# pcb.net
KiCad netlist of a schematic drawn in EasyEDA Pro
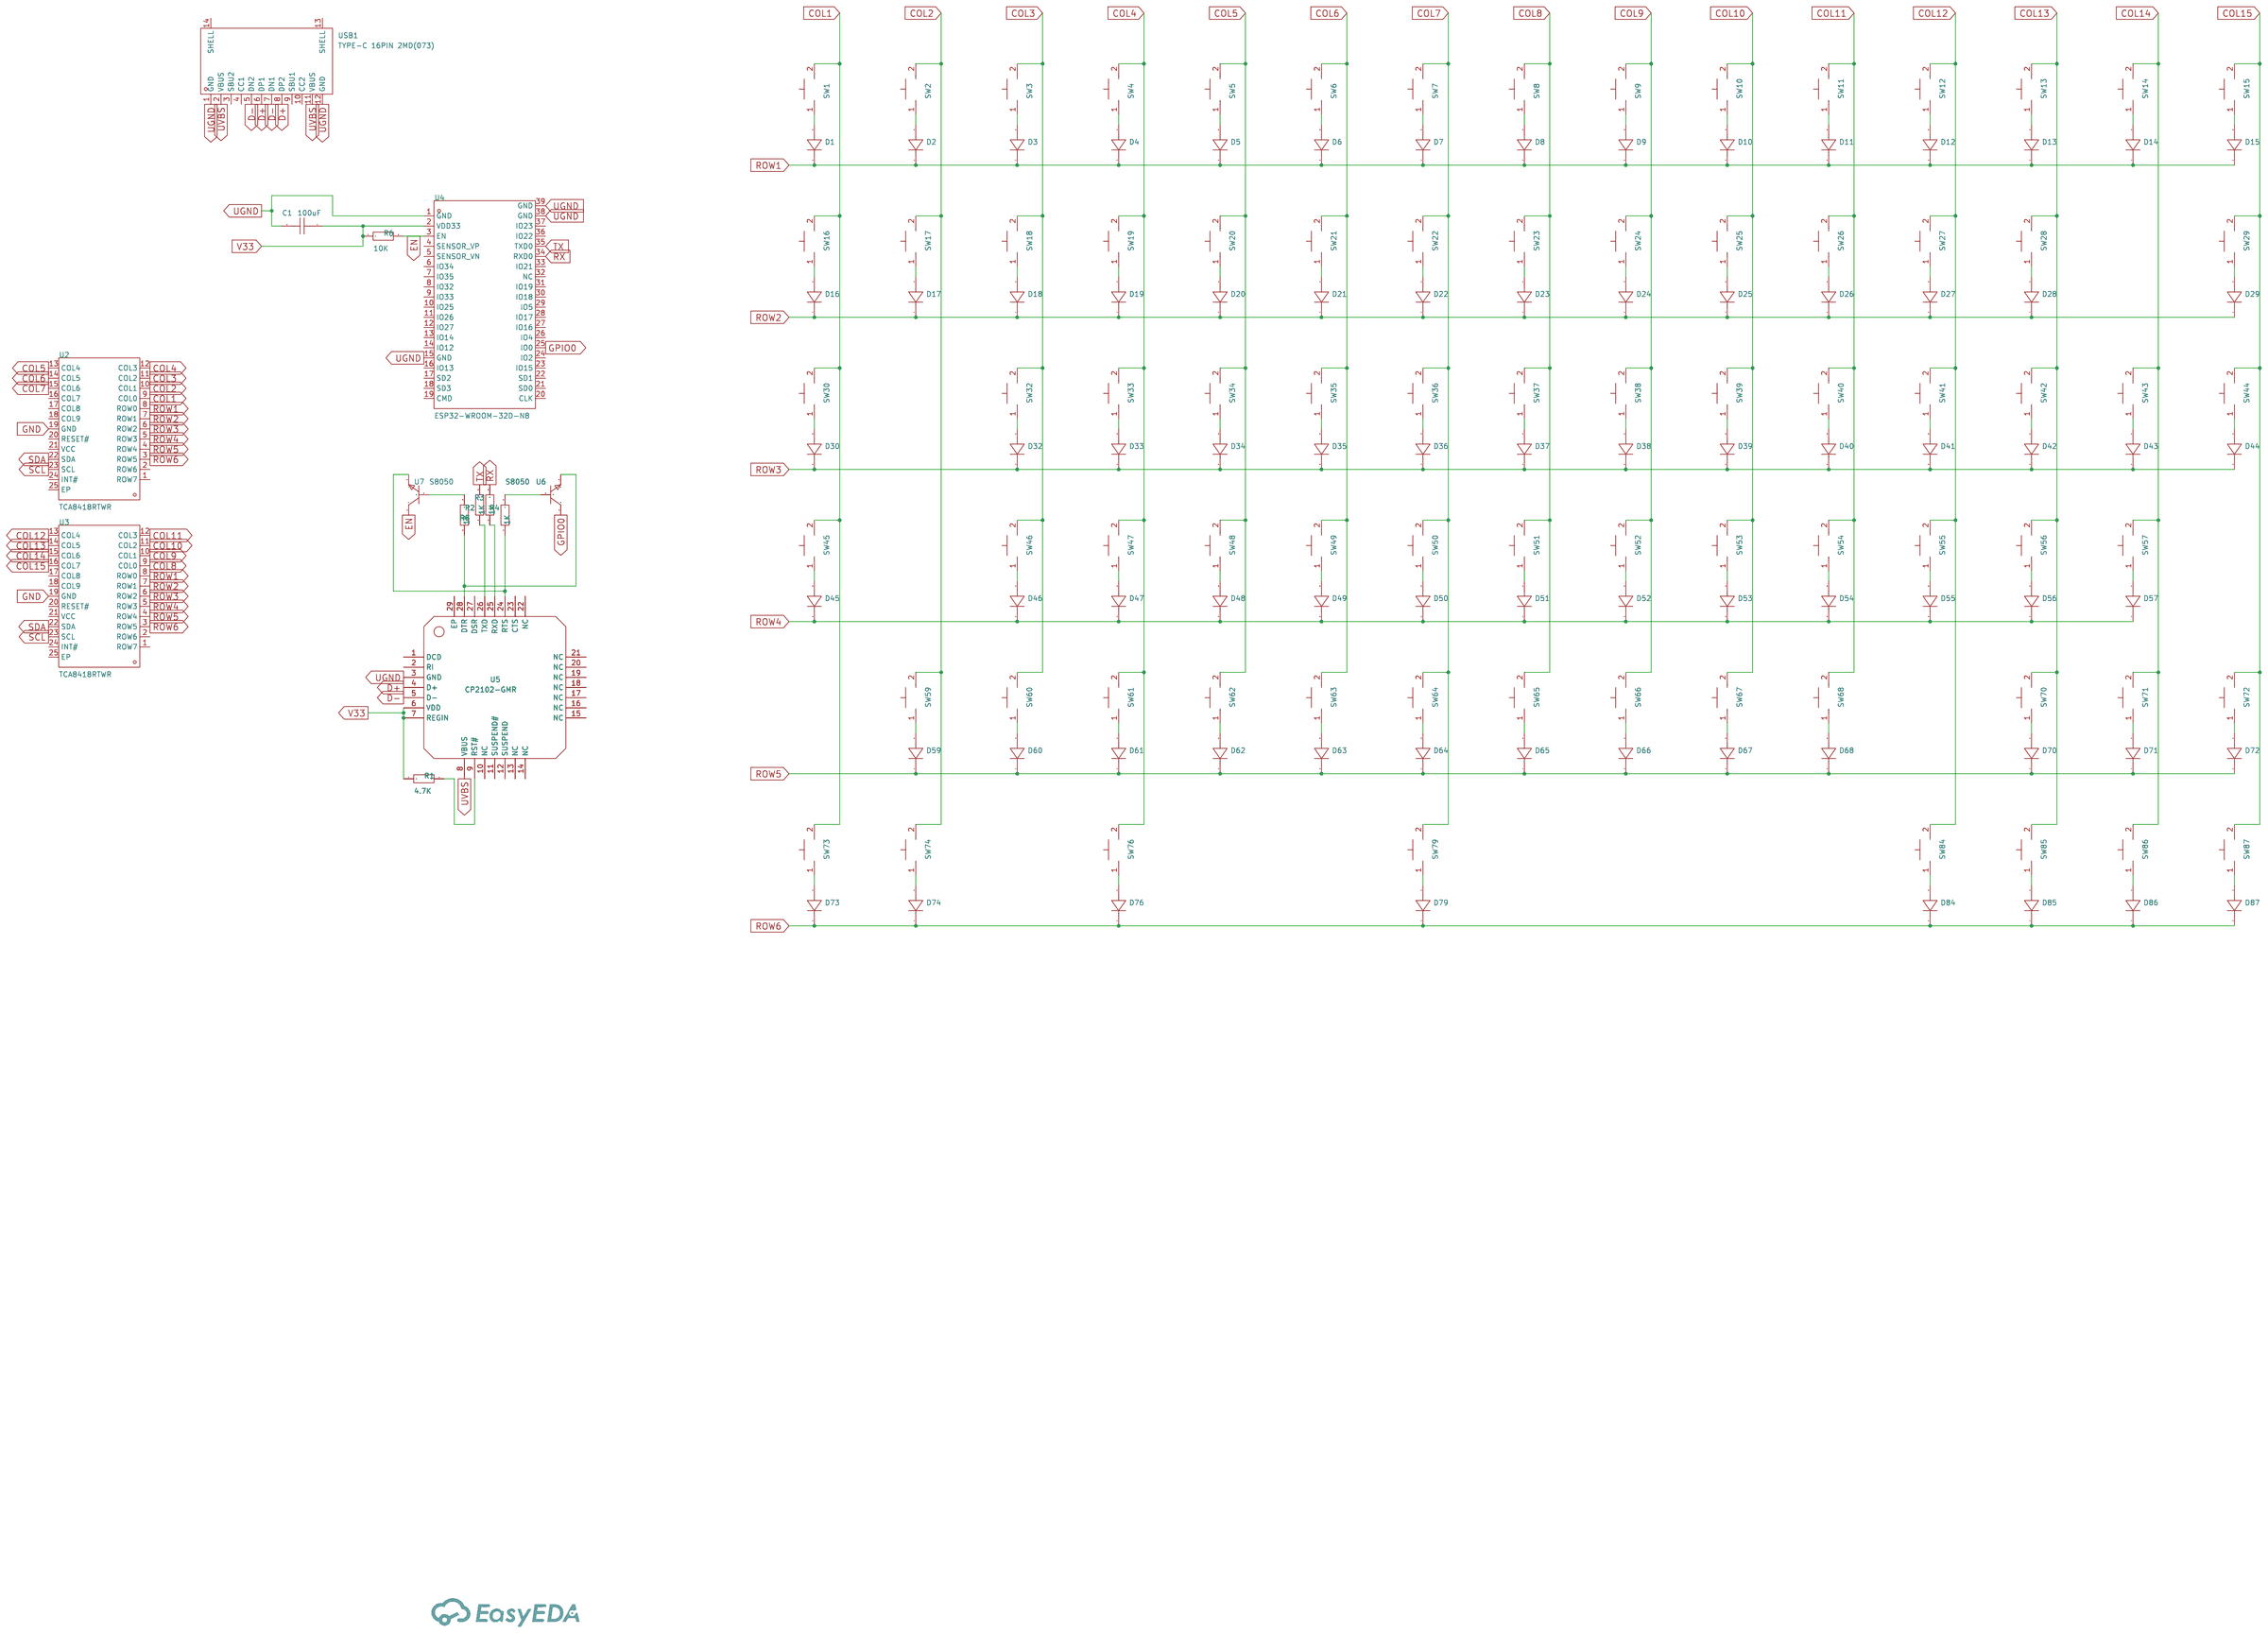
[diagram p0: schematic sheet]

(export (version "E")
  (design (tool "Eeschema 10.0.6"))
  (components
    (comp (ref "C1")
      (value "100uF")
      (footprint "easyedapro:C0603")
      (libsource (lib "easyedapro") (part "CAP"))
    )
    (comp (ref "D1")
      (value "~")
      (footprint "easyedapro:DO-41_BD2.4-L4.7-P8.70-D0.9-RD")
      (libsource (lib "easyedapro") (part "D_1N4007"))
    )
    (comp (ref "D2")
      (value "~")
      (footprint "easyedapro:DO-41_BD2.4-L4.7-P8.70-D0.9-RD")
      (libsource (lib "easyedapro") (part "D_1N4007"))
    )
    (comp (ref "D3")
      (value "~")
      (footprint "easyedapro:DO-41_BD2.4-L4.7-P8.70-D0.9-RD")
      (libsource (lib "easyedapro") (part "D_1N4007"))
    )
    (comp (ref "D4")
      (value "~")
      (footprint "easyedapro:DO-41_BD2.4-L4.7-P8.70-D0.9-RD")
      (libsource (lib "easyedapro") (part "D_1N4007"))
    )
    (comp (ref "D5")
      (value "~")
      (footprint "easyedapro:DO-41_BD2.4-L4.7-P8.70-D0.9-RD")
      (libsource (lib "easyedapro") (part "D_1N4007"))
    )
    (comp (ref "D6")
      (value "~")
      (footprint "easyedapro:DO-41_BD2.4-L4.7-P8.70-D0.9-RD")
      (libsource (lib "easyedapro") (part "D_1N4007"))
    )
    (comp (ref "D7")
      (value "~")
      (footprint "easyedapro:DO-41_BD2.4-L4.7-P8.70-D0.9-RD")
      (libsource (lib "easyedapro") (part "D_1N4007"))
    )
    (comp (ref "D8")
      (value "~")
      (footprint "easyedapro:DO-41_BD2.4-L4.7-P8.70-D0.9-RD")
      (libsource (lib "easyedapro") (part "D_1N4007"))
    )
    (comp (ref "D9")
      (value "~")
      (footprint "easyedapro:DO-41_BD2.4-L4.7-P8.70-D0.9-RD")
      (libsource (lib "easyedapro") (part "D_1N4007"))
    )
    (comp (ref "D10")
      (value "~")
      (footprint "easyedapro:DO-41_BD2.4-L4.7-P8.70-D0.9-RD")
      (libsource (lib "easyedapro") (part "D_1N4007"))
    )
    (comp (ref "D11")
      (value "~")
      (footprint "easyedapro:DO-41_BD2.4-L4.7-P8.70-D0.9-RD")
      (libsource (lib "easyedapro") (part "D_1N4007"))
    )
    (comp (ref "D12")
      (value "~")
      (footprint "easyedapro:DO-41_BD2.4-L4.7-P8.70-D0.9-RD")
      (libsource (lib "easyedapro") (part "D_1N4007"))
    )
    (comp (ref "D13")
      (value "~")
      (footprint "easyedapro:DO-41_BD2.4-L4.7-P8.70-D0.9-RD")
      (libsource (lib "easyedapro") (part "D_1N4007"))
    )
    (comp (ref "D14")
      (value "~")
      (footprint "easyedapro:DO-41_BD2.4-L4.7-P8.70-D0.9-RD")
      (libsource (lib "easyedapro") (part "D_1N4007"))
    )
    (comp (ref "D15")
      (value "~")
      (footprint "easyedapro:DO-41_BD2.4-L4.7-P8.70-D0.9-RD")
      (libsource (lib "easyedapro") (part "D_1N4007"))
    )
    (comp (ref "D16")
      (value "~")
      (footprint "easyedapro:DO-41_BD2.4-L4.7-P8.70-D0.9-RD")
      (libsource (lib "easyedapro") (part "D_1N4007"))
    )
    (comp (ref "D17")
      (value "~")
      (footprint "easyedapro:DO-41_BD2.4-L4.7-P8.70-D0.9-RD")
      (libsource (lib "easyedapro") (part "D_1N4007"))
    )
    (comp (ref "D18")
      (value "~")
      (footprint "easyedapro:DO-41_BD2.4-L4.7-P8.70-D0.9-RD")
      (libsource (lib "easyedapro") (part "D_1N4007"))
    )
    (comp (ref "D19")
      (value "~")
      (footprint "easyedapro:DO-41_BD2.4-L4.7-P8.70-D0.9-RD")
      (libsource (lib "easyedapro") (part "D_1N4007"))
    )
    (comp (ref "D20")
      (value "~")
      (footprint "easyedapro:DO-41_BD2.4-L4.7-P8.70-D0.9-RD")
      (libsource (lib "easyedapro") (part "D_1N4007"))
    )
    (comp (ref "D21")
      (value "~")
      (footprint "easyedapro:DO-41_BD2.4-L4.7-P8.70-D0.9-RD")
      (libsource (lib "easyedapro") (part "D_1N4007"))
    )
    (comp (ref "D22")
      (value "~")
      (footprint "easyedapro:DO-41_BD2.4-L4.7-P8.70-D0.9-RD")
      (libsource (lib "easyedapro") (part "D_1N4007"))
    )
    (comp (ref "D23")
      (value "~")
      (footprint "easyedapro:DO-41_BD2.4-L4.7-P8.70-D0.9-RD")
      (libsource (lib "easyedapro") (part "D_1N4007"))
    )
    (comp (ref "D24")
      (value "~")
      (footprint "easyedapro:DO-41_BD2.4-L4.7-P8.70-D0.9-RD")
      (libsource (lib "easyedapro") (part "D_1N4007"))
    )
    (comp (ref "D25")
      (value "~")
      (footprint "easyedapro:DO-41_BD2.4-L4.7-P8.70-D0.9-RD")
      (libsource (lib "easyedapro") (part "D_1N4007"))
    )
    (comp (ref "D26")
      (value "~")
      (footprint "easyedapro:DO-41_BD2.4-L4.7-P8.70-D0.9-RD")
      (libsource (lib "easyedapro") (part "D_1N4007"))
    )
    (comp (ref "D27")
      (value "~")
      (footprint "easyedapro:DO-41_BD2.4-L4.7-P8.70-D0.9-RD")
      (libsource (lib "easyedapro") (part "D_1N4007"))
    )
    (comp (ref "D28")
      (value "~")
      (footprint "easyedapro:DO-41_BD2.4-L4.7-P8.70-D0.9-RD")
      (libsource (lib "easyedapro") (part "D_1N4007"))
    )
    (comp (ref "D29")
      (value "~")
      (footprint "easyedapro:DO-41_BD2.4-L4.7-P8.70-D0.9-RD")
      (libsource (lib "easyedapro") (part "D_1N4007"))
    )
    (comp (ref "D30")
      (value "~")
      (footprint "easyedapro:DO-41_BD2.4-L4.7-P8.70-D0.9-RD")
      (libsource (lib "easyedapro") (part "D_1N4007"))
    )
    (comp (ref "D32")
      (value "~")
      (footprint "easyedapro:DO-41_BD2.4-L4.7-P8.70-D0.9-RD")
      (libsource (lib "easyedapro") (part "D_1N4007"))
    )
    (comp (ref "D33")
      (value "~")
      (footprint "easyedapro:DO-41_BD2.4-L4.7-P8.70-D0.9-RD")
      (libsource (lib "easyedapro") (part "D_1N4007"))
    )
    (comp (ref "D34")
      (value "~")
      (footprint "easyedapro:DO-41_BD2.4-L4.7-P8.70-D0.9-RD")
      (libsource (lib "easyedapro") (part "D_1N4007"))
    )
    (comp (ref "D35")
      (value "~")
      (footprint "easyedapro:DO-41_BD2.4-L4.7-P8.70-D0.9-RD")
      (libsource (lib "easyedapro") (part "D_1N4007"))
    )
    (comp (ref "D36")
      (value "~")
      (footprint "easyedapro:DO-41_BD2.4-L4.7-P8.70-D0.9-RD")
      (libsource (lib "easyedapro") (part "D_1N4007"))
    )
    (comp (ref "D37")
      (value "~")
      (footprint "easyedapro:DO-41_BD2.4-L4.7-P8.70-D0.9-RD")
      (libsource (lib "easyedapro") (part "D_1N4007"))
    )
    (comp (ref "D38")
      (value "~")
      (footprint "easyedapro:DO-41_BD2.4-L4.7-P8.70-D0.9-RD")
      (libsource (lib "easyedapro") (part "D_1N4007"))
    )
    (comp (ref "D39")
      (value "~")
      (footprint "easyedapro:DO-41_BD2.4-L4.7-P8.70-D0.9-RD")
      (libsource (lib "easyedapro") (part "D_1N4007"))
    )
    (comp (ref "D40")
      (value "~")
      (footprint "easyedapro:DO-41_BD2.4-L4.7-P8.70-D0.9-RD")
      (libsource (lib "easyedapro") (part "D_1N4007"))
    )
    (comp (ref "D41")
      (value "~")
      (footprint "easyedapro:DO-41_BD2.4-L4.7-P8.70-D0.9-RD")
      (libsource (lib "easyedapro") (part "D_1N4007"))
    )
    (comp (ref "D42")
      (value "~")
      (footprint "easyedapro:DO-41_BD2.4-L4.7-P8.70-D0.9-RD")
      (libsource (lib "easyedapro") (part "D_1N4007"))
    )
    (comp (ref "D43")
      (value "~")
      (footprint "easyedapro:DO-41_BD2.4-L4.7-P8.70-D0.9-RD")
      (libsource (lib "easyedapro") (part "D_1N4007"))
    )
    (comp (ref "D44")
      (value "~")
      (footprint "easyedapro:DO-41_BD2.4-L4.7-P8.70-D0.9-RD")
      (libsource (lib "easyedapro") (part "D_1N4007"))
    )
    (comp (ref "D45")
      (value "~")
      (footprint "easyedapro:DO-41_BD2.4-L4.7-P8.70-D0.9-RD")
      (libsource (lib "easyedapro") (part "D_1N4007"))
    )
    (comp (ref "D46")
      (value "~")
      (footprint "easyedapro:DO-41_BD2.4-L4.7-P8.70-D0.9-RD")
      (libsource (lib "easyedapro") (part "D_1N4007"))
    )
    (comp (ref "D47")
      (value "~")
      (footprint "easyedapro:DO-41_BD2.4-L4.7-P8.70-D0.9-RD")
      (libsource (lib "easyedapro") (part "D_1N4007"))
    )
    (comp (ref "D48")
      (value "~")
      (footprint "easyedapro:DO-41_BD2.4-L4.7-P8.70-D0.9-RD")
      (libsource (lib "easyedapro") (part "D_1N4007"))
    )
    (comp (ref "D49")
      (value "~")
      (footprint "easyedapro:DO-41_BD2.4-L4.7-P8.70-D0.9-RD")
      (libsource (lib "easyedapro") (part "D_1N4007"))
    )
    (comp (ref "D50")
      (value "~")
      (footprint "easyedapro:DO-41_BD2.4-L4.7-P8.70-D0.9-RD")
      (libsource (lib "easyedapro") (part "D_1N4007"))
    )
    (comp (ref "D51")
      (value "~")
      (footprint "easyedapro:DO-41_BD2.4-L4.7-P8.70-D0.9-RD")
      (libsource (lib "easyedapro") (part "D_1N4007"))
    )
    (comp (ref "D52")
      (value "~")
      (footprint "easyedapro:DO-41_BD2.4-L4.7-P8.70-D0.9-RD")
      (libsource (lib "easyedapro") (part "D_1N4007"))
    )
    (comp (ref "D53")
      (value "~")
      (footprint "easyedapro:DO-41_BD2.4-L4.7-P8.70-D0.9-RD")
      (libsource (lib "easyedapro") (part "D_1N4007"))
    )
    (comp (ref "D54")
      (value "~")
      (footprint "easyedapro:DO-41_BD2.4-L4.7-P8.70-D0.9-RD")
      (libsource (lib "easyedapro") (part "D_1N4007"))
    )
    (comp (ref "D55")
      (value "~")
      (footprint "easyedapro:DO-41_BD2.4-L4.7-P8.70-D0.9-RD")
      (libsource (lib "easyedapro") (part "D_1N4007"))
    )
    (comp (ref "D56")
      (value "~")
      (footprint "easyedapro:DO-41_BD2.4-L4.7-P8.70-D0.9-RD")
      (libsource (lib "easyedapro") (part "D_1N4007"))
    )
    (comp (ref "D57")
      (value "~")
      (footprint "easyedapro:DO-41_BD2.4-L4.7-P8.70-D0.9-RD")
      (libsource (lib "easyedapro") (part "D_1N4007"))
    )
    (comp (ref "D59")
      (value "~")
      (footprint "easyedapro:DO-41_BD2.4-L4.7-P8.70-D0.9-RD")
      (libsource (lib "easyedapro") (part "D_1N4007"))
    )
    (comp (ref "D60")
      (value "~")
      (footprint "easyedapro:DO-41_BD2.4-L4.7-P8.70-D0.9-RD")
      (libsource (lib "easyedapro") (part "D_1N4007"))
    )
    (comp (ref "D61")
      (value "~")
      (footprint "easyedapro:DO-41_BD2.4-L4.7-P8.70-D0.9-RD")
      (libsource (lib "easyedapro") (part "D_1N4007"))
    )
    (comp (ref "D62")
      (value "~")
      (footprint "easyedapro:DO-41_BD2.4-L4.7-P8.70-D0.9-RD")
      (libsource (lib "easyedapro") (part "D_1N4007"))
    )
    (comp (ref "D63")
      (value "~")
      (footprint "easyedapro:DO-41_BD2.4-L4.7-P8.70-D0.9-RD")
      (libsource (lib "easyedapro") (part "D_1N4007"))
    )
    (comp (ref "D64")
      (value "~")
      (footprint "easyedapro:DO-41_BD2.4-L4.7-P8.70-D0.9-RD")
      (libsource (lib "easyedapro") (part "D_1N4007"))
    )
    (comp (ref "D65")
      (value "~")
      (footprint "easyedapro:DO-41_BD2.4-L4.7-P8.70-D0.9-RD")
      (libsource (lib "easyedapro") (part "D_1N4007"))
    )
    (comp (ref "D66")
      (value "~")
      (footprint "easyedapro:DO-41_BD2.4-L4.7-P8.70-D0.9-RD")
      (libsource (lib "easyedapro") (part "D_1N4007"))
    )
    (comp (ref "D67")
      (value "~")
      (footprint "easyedapro:DO-41_BD2.4-L4.7-P8.70-D0.9-RD")
      (libsource (lib "easyedapro") (part "D_1N4007"))
    )
    (comp (ref "D68")
      (value "~")
      (footprint "easyedapro:DO-41_BD2.4-L4.7-P8.70-D0.9-RD")
      (libsource (lib "easyedapro") (part "D_1N4007"))
    )
    (comp (ref "D70")
      (value "~")
      (footprint "easyedapro:DO-41_BD2.4-L4.7-P8.70-D0.9-RD")
      (libsource (lib "easyedapro") (part "D_1N4007"))
    )
    (comp (ref "D71")
      (value "~")
      (footprint "easyedapro:DO-41_BD2.4-L4.7-P8.70-D0.9-RD")
      (libsource (lib "easyedapro") (part "D_1N4007"))
    )
    (comp (ref "D72")
      (value "~")
      (footprint "easyedapro:DO-41_BD2.4-L4.7-P8.70-D0.9-RD")
      (libsource (lib "easyedapro") (part "D_1N4007"))
    )
    (comp (ref "D73")
      (value "~")
      (footprint "easyedapro:DO-41_BD2.4-L4.7-P8.70-D0.9-RD")
      (libsource (lib "easyedapro") (part "D_1N4007"))
    )
    (comp (ref "D74")
      (value "~")
      (footprint "easyedapro:DO-41_BD2.4-L4.7-P8.70-D0.9-RD")
      (libsource (lib "easyedapro") (part "D_1N4007"))
    )
    (comp (ref "D76")
      (value "~")
      (footprint "easyedapro:DO-41_BD2.4-L4.7-P8.70-D0.9-RD")
      (libsource (lib "easyedapro") (part "D_1N4007"))
    )
    (comp (ref "D79")
      (value "~")
      (footprint "easyedapro:DO-41_BD2.4-L4.7-P8.70-D0.9-RD")
      (libsource (lib "easyedapro") (part "D_1N4007"))
    )
    (comp (ref "D84")
      (value "~")
      (footprint "easyedapro:DO-41_BD2.4-L4.7-P8.70-D0.9-RD")
      (libsource (lib "easyedapro") (part "D_1N4007"))
    )
    (comp (ref "D85")
      (value "~")
      (footprint "easyedapro:DO-41_BD2.4-L4.7-P8.70-D0.9-RD")
      (libsource (lib "easyedapro") (part "D_1N4007"))
    )
    (comp (ref "D86")
      (value "~")
      (footprint "easyedapro:DO-41_BD2.4-L4.7-P8.70-D0.9-RD")
      (libsource (lib "easyedapro") (part "D_1N4007"))
    )
    (comp (ref "D87")
      (value "~")
      (footprint "easyedapro:DO-41_BD2.4-L4.7-P8.70-D0.9-RD")
      (libsource (lib "easyedapro") (part "D_1N4007"))
    )
    (comp (ref "R1")
      (value "4.7K")
      (footprint "easyedapro:R0603")
      (libsource (lib "easyedapro") (part "Res"))
    )
    (comp (ref "R2") (value "1K") (footprint "easyedapro:R0603") (libsource (lib "easyedapro") (part "Res")))
    (comp (ref "R3") (value "1K") (footprint "easyedapro:R0603") (libsource (lib "easyedapro") (part "Res")))
    (comp (ref "R4") (value "1K") (footprint "easyedapro:R0603") (libsource (lib "easyedapro") (part "Res")))
    (comp (ref "R5") (value "1K") (footprint "easyedapro:R0603") (libsource (lib "easyedapro") (part "Res")))
    (comp (ref "R6") (value "10K") (footprint "easyedapro:R0603") (libsource (lib "easyedapro") (part "Res")))
    (comp (ref "SW1")
      (value "CPG151101S11-16")
      (footprint "easyedapro:SMD_KEYBOARD-SW")
      (fields (field (name "Manufacturer") "HanElectricity(瀚源)"))
      (libsource (lib "easyedapro") (part "CPG151101S11-16_C41430893"))
    )
    (comp (ref "SW2")
      (value "CPG151101S11-16")
      (footprint "easyedapro:SMD_KEYBOARD-SW")
      (fields (field (name "Manufacturer") "HanElectricity(瀚源)"))
      (libsource (lib "easyedapro") (part "CPG151101S11-16_C41430893"))
    )
    (comp (ref "SW3")
      (value "CPG151101S11-16")
      (footprint "easyedapro:SMD_KEYBOARD-SW")
      (fields (field (name "Manufacturer") "HanElectricity(瀚源)"))
      (libsource (lib "easyedapro") (part "CPG151101S11-16_C41430893"))
    )
    (comp (ref "SW4")
      (value "CPG151101S11-16")
      (footprint "easyedapro:SMD_KEYBOARD-SW")
      (fields (field (name "Manufacturer") "HanElectricity(瀚源)"))
      (libsource (lib "easyedapro") (part "CPG151101S11-16_C41430893"))
    )
    (comp (ref "SW5")
      (value "CPG151101S11-16")
      (footprint "easyedapro:SMD_KEYBOARD-SW")
      (fields (field (name "Manufacturer") "HanElectricity(瀚源)"))
      (libsource (lib "easyedapro") (part "CPG151101S11-16_C41430893"))
    )
    (comp (ref "SW6")
      (value "CPG151101S11-16")
      (footprint "easyedapro:SMD_KEYBOARD-SW")
      (fields (field (name "Manufacturer") "HanElectricity(瀚源)"))
      (libsource (lib "easyedapro") (part "CPG151101S11-16_C41430893"))
    )
    (comp (ref "SW7")
      (value "CPG151101S11-16")
      (footprint "easyedapro:SMD_KEYBOARD-SW")
      (fields (field (name "Manufacturer") "HanElectricity(瀚源)"))
      (libsource (lib "easyedapro") (part "CPG151101S11-16_C41430893"))
    )
    (comp (ref "SW8")
      (value "CPG151101S11-16")
      (footprint "easyedapro:SMD_KEYBOARD-SW")
      (fields (field (name "Manufacturer") "HanElectricity(瀚源)"))
      (libsource (lib "easyedapro") (part "CPG151101S11-16_C41430893"))
    )
    (comp (ref "SW9")
      (value "CPG151101S11-16")
      (footprint "easyedapro:SMD_KEYBOARD-SW")
      (fields (field (name "Manufacturer") "HanElectricity(瀚源)"))
      (libsource (lib "easyedapro") (part "CPG151101S11-16_C41430893"))
    )
    (comp (ref "SW10")
      (value "CPG151101S11-16")
      (footprint "easyedapro:SMD_KEYBOARD-SW")
      (fields (field (name "Manufacturer") "HanElectricity(瀚源)"))
      (libsource (lib "easyedapro") (part "CPG151101S11-16_C41430893"))
    )
    (comp (ref "SW11")
      (value "CPG151101S11-16")
      (footprint "easyedapro:SMD_KEYBOARD-SW")
      (fields (field (name "Manufacturer") "HanElectricity(瀚源)"))
      (libsource (lib "easyedapro") (part "CPG151101S11-16_C41430893"))
    )
    (comp (ref "SW12")
      (value "CPG151101S11-16")
      (footprint "easyedapro:SMD_KEYBOARD-SW")
      (fields (field (name "Manufacturer") "HanElectricity(瀚源)"))
      (libsource (lib "easyedapro") (part "CPG151101S11-16_C41430893"))
    )
    (comp (ref "SW13")
      (value "CPG151101S11-16")
      (footprint "easyedapro:SMD_KEYBOARD-SW")
      (fields (field (name "Manufacturer") "HanElectricity(瀚源)"))
      (libsource (lib "easyedapro") (part "CPG151101S11-16_C41430893"))
    )
    (comp (ref "SW14")
      (value "CPG151101S11-16")
      (footprint "easyedapro:SMD_KEYBOARD-SW")
      (fields (field (name "Manufacturer") "HanElectricity(瀚源)"))
      (libsource (lib "easyedapro") (part "CPG151101S11-16_C41430893"))
    )
    (comp (ref "SW15")
      (value "CPG151101S11-16")
      (footprint "easyedapro:SMD_KEYBOARD-SW")
      (fields (field (name "Manufacturer") "HanElectricity(瀚源)"))
      (libsource (lib "easyedapro") (part "CPG151101S11-16_C41430893"))
    )
    (comp (ref "SW16")
      (value "CPG151101S11-16")
      (footprint "easyedapro:SMD_KEYBOARD-SW")
      (fields (field (name "Manufacturer") "HanElectricity(瀚源)"))
      (libsource (lib "easyedapro") (part "CPG151101S11-16_C41430893"))
    )
    (comp (ref "SW17")
      (value "CPG151101S11-16")
      (footprint "easyedapro:SMD_KEYBOARD-SW")
      (fields (field (name "Manufacturer") "HanElectricity(瀚源)"))
      (libsource (lib "easyedapro") (part "CPG151101S11-16_C41430893"))
    )
    (comp (ref "SW18")
      (value "CPG151101S11-16")
      (footprint "easyedapro:SMD_KEYBOARD-SW")
      (fields (field (name "Manufacturer") "HanElectricity(瀚源)"))
      (libsource (lib "easyedapro") (part "CPG151101S11-16_C41430893"))
    )
    (comp (ref "SW19")
      (value "CPG151101S11-16")
      (footprint "easyedapro:SMD_KEYBOARD-SW")
      (fields (field (name "Manufacturer") "HanElectricity(瀚源)"))
      (libsource (lib "easyedapro") (part "CPG151101S11-16_C41430893"))
    )
    (comp (ref "SW20")
      (value "CPG151101S11-16")
      (footprint "easyedapro:SMD_KEYBOARD-SW")
      (fields (field (name "Manufacturer") "HanElectricity(瀚源)"))
      (libsource (lib "easyedapro") (part "CPG151101S11-16_C41430893"))
    )
    (comp (ref "SW21")
      (value "CPG151101S11-16")
      (footprint "easyedapro:SMD_KEYBOARD-SW")
      (fields (field (name "Manufacturer") "HanElectricity(瀚源)"))
      (libsource (lib "easyedapro") (part "CPG151101S11-16_C41430893"))
    )
    (comp (ref "SW22")
      (value "CPG151101S11-16")
      (footprint "easyedapro:SMD_KEYBOARD-SW")
      (fields (field (name "Manufacturer") "HanElectricity(瀚源)"))
      (libsource (lib "easyedapro") (part "CPG151101S11-16_C41430893"))
    )
    (comp (ref "SW23")
      (value "CPG151101S11-16")
      (footprint "easyedapro:SMD_KEYBOARD-SW")
      (fields (field (name "Manufacturer") "HanElectricity(瀚源)"))
      (libsource (lib "easyedapro") (part "CPG151101S11-16_C41430893"))
    )
    (comp (ref "SW24")
      (value "CPG151101S11-16")
      (footprint "easyedapro:SMD_KEYBOARD-SW")
      (fields (field (name "Manufacturer") "HanElectricity(瀚源)"))
      (libsource (lib "easyedapro") (part "CPG151101S11-16_C41430893"))
    )
    (comp (ref "SW25")
      (value "CPG151101S11-16")
      (footprint "easyedapro:SMD_KEYBOARD-SW")
      (fields (field (name "Manufacturer") "HanElectricity(瀚源)"))
      (libsource (lib "easyedapro") (part "CPG151101S11-16_C41430893"))
    )
    (comp (ref "SW26")
      (value "CPG151101S11-16")
      (footprint "easyedapro:SMD_KEYBOARD-SW")
      (fields (field (name "Manufacturer") "HanElectricity(瀚源)"))
      (libsource (lib "easyedapro") (part "CPG151101S11-16_C41430893"))
    )
    (comp (ref "SW27")
      (value "CPG151101S11-16")
      (footprint "easyedapro:SMD_KEYBOARD-SW")
      (fields (field (name "Manufacturer") "HanElectricity(瀚源)"))
      (libsource (lib "easyedapro") (part "CPG151101S11-16_C41430893"))
    )
    (comp (ref "SW28")
      (value "CPG151101S11-16")
      (footprint "easyedapro:SMD_KEYBOARD-SW")
      (fields (field (name "Manufacturer") "HanElectricity(瀚源)"))
      (libsource (lib "easyedapro") (part "CPG151101S11-16_C41430893"))
    )
    (comp (ref "SW29")
      (value "CPG151101S11-16")
      (footprint "easyedapro:SMD_KEYBOARD-SW")
      (fields (field (name "Manufacturer") "HanElectricity(瀚源)"))
      (libsource (lib "easyedapro") (part "CPG151101S11-16_C41430893"))
    )
    (comp (ref "SW30")
      (value "CPG151101S11-16")
      (footprint "easyedapro:SMD_KEYBOARD-SW")
      (fields (field (name "Manufacturer") "HanElectricity(瀚源)"))
      (libsource (lib "easyedapro") (part "CPG151101S11-16_C41430893"))
    )
    (comp (ref "SW32")
      (value "CPG151101S11-16")
      (footprint "easyedapro:SMD_KEYBOARD-SW")
      (fields (field (name "Manufacturer") "HanElectricity(瀚源)"))
      (libsource (lib "easyedapro") (part "CPG151101S11-16_C41430893"))
    )
    (comp (ref "SW33")
      (value "CPG151101S11-16")
      (footprint "easyedapro:SMD_KEYBOARD-SW")
      (fields (field (name "Manufacturer") "HanElectricity(瀚源)"))
      (libsource (lib "easyedapro") (part "CPG151101S11-16_C41430893"))
    )
    (comp (ref "SW34")
      (value "CPG151101S11-16")
      (footprint "easyedapro:SMD_KEYBOARD-SW")
      (fields (field (name "Manufacturer") "HanElectricity(瀚源)"))
      (libsource (lib "easyedapro") (part "CPG151101S11-16_C41430893"))
    )
    (comp (ref "SW35")
      (value "CPG151101S11-16")
      (footprint "easyedapro:SMD_KEYBOARD-SW")
      (fields (field (name "Manufacturer") "HanElectricity(瀚源)"))
      (libsource (lib "easyedapro") (part "CPG151101S11-16_C41430893"))
    )
    (comp (ref "SW36")
      (value "CPG151101S11-16")
      (footprint "easyedapro:SMD_KEYBOARD-SW")
      (fields (field (name "Manufacturer") "HanElectricity(瀚源)"))
      (libsource (lib "easyedapro") (part "CPG151101S11-16_C41430893"))
    )
    (comp (ref "SW37")
      (value "CPG151101S11-16")
      (footprint "easyedapro:SMD_KEYBOARD-SW")
      (fields (field (name "Manufacturer") "HanElectricity(瀚源)"))
      (libsource (lib "easyedapro") (part "CPG151101S11-16_C41430893"))
    )
    (comp (ref "SW38")
      (value "CPG151101S11-16")
      (footprint "easyedapro:SMD_KEYBOARD-SW")
      (fields (field (name "Manufacturer") "HanElectricity(瀚源)"))
      (libsource (lib "easyedapro") (part "CPG151101S11-16_C41430893"))
    )
    (comp (ref "SW39")
      (value "CPG151101S11-16")
      (footprint "easyedapro:SMD_KEYBOARD-SW")
      (fields (field (name "Manufacturer") "HanElectricity(瀚源)"))
      (libsource (lib "easyedapro") (part "CPG151101S11-16_C41430893"))
    )
    (comp (ref "SW40")
      (value "CPG151101S11-16")
      (footprint "easyedapro:SMD_KEYBOARD-SW")
      (fields (field (name "Manufacturer") "HanElectricity(瀚源)"))
      (libsource (lib "easyedapro") (part "CPG151101S11-16_C41430893"))
    )
    (comp (ref "SW41")
      (value "CPG151101S11-16")
      (footprint "easyedapro:SMD_KEYBOARD-SW")
      (fields (field (name "Manufacturer") "HanElectricity(瀚源)"))
      (libsource (lib "easyedapro") (part "CPG151101S11-16_C41430893"))
    )
    (comp (ref "SW42")
      (value "CPG151101S11-16")
      (footprint "easyedapro:SMD_KEYBOARD-SW")
      (fields (field (name "Manufacturer") "HanElectricity(瀚源)"))
      (libsource (lib "easyedapro") (part "CPG151101S11-16_C41430893"))
    )
    (comp (ref "SW43")
      (value "CPG151101S11-16")
      (footprint "easyedapro:SMD_KEYBOARD-SW")
      (fields (field (name "Manufacturer") "HanElectricity(瀚源)"))
      (libsource (lib "easyedapro") (part "CPG151101S11-16_C41430893"))
    )
    (comp (ref "SW44")
      (value "CPG151101S11-16")
      (footprint "easyedapro:SMD_KEYBOARD-SW")
      (fields (field (name "Manufacturer") "HanElectricity(瀚源)"))
      (libsource (lib "easyedapro") (part "CPG151101S11-16_C41430893"))
    )
    (comp (ref "SW45")
      (value "CPG151101S11-16")
      (footprint "easyedapro:SMD_KEYBOARD-SW")
      (fields (field (name "Manufacturer") "HanElectricity(瀚源)"))
      (libsource (lib "easyedapro") (part "CPG151101S11-16_C41430893"))
    )
    (comp (ref "SW46")
      (value "CPG151101S11-16")
      (footprint "easyedapro:SMD_KEYBOARD-SW")
      (fields (field (name "Manufacturer") "HanElectricity(瀚源)"))
      (libsource (lib "easyedapro") (part "CPG151101S11-16_C41430893"))
    )
    (comp (ref "SW47")
      (value "CPG151101S11-16")
      (footprint "easyedapro:SMD_KEYBOARD-SW")
      (fields (field (name "Manufacturer") "HanElectricity(瀚源)"))
      (libsource (lib "easyedapro") (part "CPG151101S11-16_C41430893"))
    )
    (comp (ref "SW48")
      (value "CPG151101S11-16")
      (footprint "easyedapro:SMD_KEYBOARD-SW")
      (fields (field (name "Manufacturer") "HanElectricity(瀚源)"))
      (libsource (lib "easyedapro") (part "CPG151101S11-16_C41430893"))
    )
    (comp (ref "SW49")
      (value "CPG151101S11-16")
      (footprint "easyedapro:SMD_KEYBOARD-SW")
      (fields (field (name "Manufacturer") "HanElectricity(瀚源)"))
      (libsource (lib "easyedapro") (part "CPG151101S11-16_C41430893"))
    )
    (comp (ref "SW50")
      (value "CPG151101S11-16")
      (footprint "easyedapro:SMD_KEYBOARD-SW")
      (fields (field (name "Manufacturer") "HanElectricity(瀚源)"))
      (libsource (lib "easyedapro") (part "CPG151101S11-16_C41430893"))
    )
    (comp (ref "SW51")
      (value "CPG151101S11-16")
      (footprint "easyedapro:SMD_KEYBOARD-SW")
      (fields (field (name "Manufacturer") "HanElectricity(瀚源)"))
      (libsource (lib "easyedapro") (part "CPG151101S11-16_C41430893"))
    )
    (comp (ref "SW52")
      (value "CPG151101S11-16")
      (footprint "easyedapro:SMD_KEYBOARD-SW")
      (fields (field (name "Manufacturer") "HanElectricity(瀚源)"))
      (libsource (lib "easyedapro") (part "CPG151101S11-16_C41430893"))
    )
    (comp (ref "SW53")
      (value "CPG151101S11-16")
      (footprint "easyedapro:SMD_KEYBOARD-SW")
      (fields (field (name "Manufacturer") "HanElectricity(瀚源)"))
      (libsource (lib "easyedapro") (part "CPG151101S11-16_C41430893"))
    )
    (comp (ref "SW54")
      (value "CPG151101S11-16")
      (footprint "easyedapro:SMD_KEYBOARD-SW")
      (fields (field (name "Manufacturer") "HanElectricity(瀚源)"))
      (libsource (lib "easyedapro") (part "CPG151101S11-16_C41430893"))
    )
    (comp (ref "SW55")
      (value "CPG151101S11-16")
      (footprint "easyedapro:SMD_KEYBOARD-SW")
      (fields (field (name "Manufacturer") "HanElectricity(瀚源)"))
      (libsource (lib "easyedapro") (part "CPG151101S11-16_C41430893"))
    )
    (comp (ref "SW56")
      (value "CPG151101S11-16")
      (footprint "easyedapro:SMD_KEYBOARD-SW")
      (fields (field (name "Manufacturer") "HanElectricity(瀚源)"))
      (libsource (lib "easyedapro") (part "CPG151101S11-16_C41430893"))
    )
    (comp (ref "SW57")
      (value "CPG151101S11-16")
      (footprint "easyedapro:SMD_KEYBOARD-SW")
      (fields (field (name "Manufacturer") "HanElectricity(瀚源)"))
      (libsource (lib "easyedapro") (part "CPG151101S11-16_C41430893"))
    )
    (comp (ref "SW59")
      (value "CPG151101S11-16")
      (footprint "easyedapro:SMD_KEYBOARD-SW")
      (fields (field (name "Manufacturer") "HanElectricity(瀚源)"))
      (libsource (lib "easyedapro") (part "CPG151101S11-16_C41430893"))
    )
    (comp (ref "SW60")
      (value "CPG151101S11-16")
      (footprint "easyedapro:SMD_KEYBOARD-SW")
      (fields (field (name "Manufacturer") "HanElectricity(瀚源)"))
      (libsource (lib "easyedapro") (part "CPG151101S11-16_C41430893"))
    )
    (comp (ref "SW61")
      (value "CPG151101S11-16")
      (footprint "easyedapro:SMD_KEYBOARD-SW")
      (fields (field (name "Manufacturer") "HanElectricity(瀚源)"))
      (libsource (lib "easyedapro") (part "CPG151101S11-16_C41430893"))
    )
    (comp (ref "SW62")
      (value "CPG151101S11-16")
      (footprint "easyedapro:SMD_KEYBOARD-SW")
      (fields (field (name "Manufacturer") "HanElectricity(瀚源)"))
      (libsource (lib "easyedapro") (part "CPG151101S11-16_C41430893"))
    )
    (comp (ref "SW63")
      (value "CPG151101S11-16")
      (footprint "easyedapro:SMD_KEYBOARD-SW")
      (fields (field (name "Manufacturer") "HanElectricity(瀚源)"))
      (libsource (lib "easyedapro") (part "CPG151101S11-16_C41430893"))
    )
    (comp (ref "SW64")
      (value "CPG151101S11-16")
      (footprint "easyedapro:SMD_KEYBOARD-SW")
      (fields (field (name "Manufacturer") "HanElectricity(瀚源)"))
      (libsource (lib "easyedapro") (part "CPG151101S11-16_C41430893"))
    )
    (comp (ref "SW65")
      (value "CPG151101S11-16")
      (footprint "easyedapro:SMD_KEYBOARD-SW")
      (fields (field (name "Manufacturer") "HanElectricity(瀚源)"))
      (libsource (lib "easyedapro") (part "CPG151101S11-16_C41430893"))
    )
    (comp (ref "SW66")
      (value "CPG151101S11-16")
      (footprint "easyedapro:SMD_KEYBOARD-SW")
      (fields (field (name "Manufacturer") "HanElectricity(瀚源)"))
      (libsource (lib "easyedapro") (part "CPG151101S11-16_C41430893"))
    )
    (comp (ref "SW67")
      (value "CPG151101S11-16")
      (footprint "easyedapro:SMD_KEYBOARD-SW")
      (fields (field (name "Manufacturer") "HanElectricity(瀚源)"))
      (libsource (lib "easyedapro") (part "CPG151101S11-16_C41430893"))
    )
    (comp (ref "SW68")
      (value "CPG151101S11-16")
      (footprint "easyedapro:SMD_KEYBOARD-SW")
      (fields (field (name "Manufacturer") "HanElectricity(瀚源)"))
      (libsource (lib "easyedapro") (part "CPG151101S11-16_C41430893"))
    )
    (comp (ref "SW70")
      (value "CPG151101S11-16")
      (footprint "easyedapro:SMD_KEYBOARD-SW")
      (fields (field (name "Manufacturer") "HanElectricity(瀚源)"))
      (libsource (lib "easyedapro") (part "CPG151101S11-16_C41430893"))
    )
    (comp (ref "SW71")
      (value "CPG151101S11-16")
      (footprint "easyedapro:SMD_KEYBOARD-SW")
      (fields (field (name "Manufacturer") "HanElectricity(瀚源)"))
      (libsource (lib "easyedapro") (part "CPG151101S11-16_C41430893"))
    )
    (comp (ref "SW72")
      (value "CPG151101S11-16")
      (footprint "easyedapro:SMD_KEYBOARD-SW")
      (fields (field (name "Manufacturer") "HanElectricity(瀚源)"))
      (libsource (lib "easyedapro") (part "CPG151101S11-16_C41430893"))
    )
    (comp (ref "SW73")
      (value "CPG151101S11-16")
      (footprint "easyedapro:SMD_KEYBOARD-SW")
      (fields (field (name "Manufacturer") "HanElectricity(瀚源)"))
      (libsource (lib "easyedapro") (part "CPG151101S11-16_C41430893"))
    )
    (comp (ref "SW74")
      (value "CPG151101S11-16")
      (footprint "easyedapro:SMD_KEYBOARD-SW")
      (fields (field (name "Manufacturer") "HanElectricity(瀚源)"))
      (libsource (lib "easyedapro") (part "CPG151101S11-16_C41430893"))
    )
    (comp (ref "SW76")
      (value "CPG151101S11-16")
      (footprint "easyedapro:SMD_KEYBOARD-SW")
      (fields (field (name "Manufacturer") "HanElectricity(瀚源)"))
      (libsource (lib "easyedapro") (part "CPG151101S11-16_C41430893"))
    )
    (comp (ref "SW79")
      (value "CPG151101S11-16")
      (footprint "easyedapro:SMD_KEYBOARD-SW")
      (fields (field (name "Manufacturer") "HanElectricity(瀚源)"))
      (libsource (lib "easyedapro") (part "CPG151101S11-16_C41430893"))
    )
    (comp (ref "SW84")
      (value "CPG151101S11-16")
      (footprint "easyedapro:SMD_KEYBOARD-SW")
      (fields (field (name "Manufacturer") "HanElectricity(瀚源)"))
      (libsource (lib "easyedapro") (part "CPG151101S11-16_C41430893"))
    )
    (comp (ref "SW85")
      (value "CPG151101S11-16")
      (footprint "easyedapro:SMD_KEYBOARD-SW")
      (fields (field (name "Manufacturer") "HanElectricity(瀚源)"))
      (libsource (lib "easyedapro") (part "CPG151101S11-16_C41430893"))
    )
    (comp (ref "SW86")
      (value "CPG151101S11-16")
      (footprint "easyedapro:SMD_KEYBOARD-SW")
      (fields (field (name "Manufacturer") "HanElectricity(瀚源)"))
      (libsource (lib "easyedapro") (part "CPG151101S11-16_C41430893"))
    )
    (comp (ref "SW87")
      (value "CPG151101S11-16")
      (footprint "easyedapro:SMD_KEYBOARD-SW")
      (fields (field (name "Manufacturer") "HanElectricity(瀚源)"))
      (libsource (lib "easyedapro") (part "CPG151101S11-16_C41430893"))
    )
    (comp (ref "U2")
      (value "TCA8418RTWR")
      (footprint "easyedapro:WQFN-24_L4.0-W4.0-P0.50-TL-EP2.5")
      (fields (field (name "Manufacturer") "TI(德州仪器)"))
      (libsource (lib "easyedapro") (part "TCA8418RTWR"))
    )
    (comp (ref "U3")
      (value "TCA8418RTWR")
      (footprint "easyedapro:WQFN-24_L4.0-W4.0-P0.50-TL-EP2.5")
      (fields (field (name "Manufacturer") "TI(德州仪器)"))
      (libsource (lib "easyedapro") (part "TCA8418RTWR"))
    )
    (comp (ref "U4")
      (value "ESP32-WROOM-32D-N8")
      (footprint "easyedapro:WIFIM-SMD_39P-L25.5-W18.0-P1.27")
      (fields (field (name "Manufacturer") "ESPRESSIF(乐鑫)"))
      (libsource (lib "easyedapro") (part "ESP32-WROOM-32D(8MB)"))
    )
    (comp (ref "U5")
      (value "CP2102-GMR")
      (footprint "easyedapro:WQFN-28_L5.0-W5.0-P0.50-BL-EP3.2")
      (fields (field (name "Manufacturer") "SKYWORKS/SILICON LABS(芯科)"))
      (libsource (lib "easyedapro") (part "CP2102-GMR"))
    )
    (comp (ref "U6")
      (value "S8050")
      (footprint "easyedapro:SOT-23-3_L2.9-W1.3-P0.95-LS2.4-BR")
      (fields (field (name "Manufacturer") "LJ(朗捷）"))
      (libsource (lib "easyedapro") (part "S8050_C18195380"))
    )
    (comp (ref "U7")
      (value "S8050")
      (footprint "easyedapro:SOT-23-3_L2.9-W1.3-P0.95-LS2.4-BR")
      (fields (field (name "Manufacturer") "LJ(朗捷）"))
      (libsource (lib "easyedapro") (part "S8050_C18195380"))
    )
    (comp (ref "USB1")
      (value "TYPE-C 16PIN 2MD(073)")
      (footprint "easyedapro:USB-C-SMD_TYPE-C-6PIN-2MD-073")
      (fields (field (name "Manufacturer") "SHOU HAN(首韩)"))
      (libsource (lib "easyedapro") (part "TYPE-C 16PIN 2MD(073)"))
    )
  )
  (nets
    (net (code "1") (name "COL1") (class "Default")
      (node (ref "SW1") (pin "2") (pinfunction "2_2") (pintype "input"))
      (node (ref "SW16") (pin "2") (pinfunction "2_2") (pintype "input"))
      (node (ref "SW30") (pin "2") (pinfunction "2_2") (pintype "input"))
      (node (ref "SW45") (pin "2") (pinfunction "2_2") (pintype "input"))
      (node (ref "SW73") (pin "2") (pinfunction "2_2") (pintype "input"))
      (node (ref "U2") (pin "9") (pinfunction "COL0_9") (pintype "unspecified"))
    )
    (net (code "2") (name "COL2") (class "Default")
      (node (ref "SW17") (pin "2") (pinfunction "2_2") (pintype "input"))
      (node (ref "SW2") (pin "2") (pinfunction "2_2") (pintype "input"))
      (node (ref "SW59") (pin "2") (pinfunction "2_2") (pintype "input"))
      (node (ref "SW74") (pin "2") (pinfunction "2_2") (pintype "input"))
      (node (ref "U2") (pin "10") (pinfunction "COL1_10") (pintype "unspecified"))
    )
    (net (code "3") (name "COL3") (class "Default")
      (node (ref "SW18") (pin "2") (pinfunction "2_2") (pintype "input"))
      (node (ref "SW3") (pin "2") (pinfunction "2_2") (pintype "input"))
      (node (ref "SW32") (pin "2") (pinfunction "2_2") (pintype "input"))
      (node (ref "SW46") (pin "2") (pinfunction "2_2") (pintype "input"))
      (node (ref "SW60") (pin "2") (pinfunction "2_2") (pintype "input"))
      (node (ref "U2") (pin "11") (pinfunction "COL2_11") (pintype "unspecified"))
    )
    (net (code "4") (name "COL4") (class "Default")
      (node (ref "SW19") (pin "2") (pinfunction "2_2") (pintype "input"))
      (node (ref "SW33") (pin "2") (pinfunction "2_2") (pintype "input"))
      (node (ref "SW4") (pin "2") (pinfunction "2_2") (pintype "input"))
      (node (ref "SW47") (pin "2") (pinfunction "2_2") (pintype "input"))
      (node (ref "SW61") (pin "2") (pinfunction "2_2") (pintype "input"))
      (node (ref "SW76") (pin "2") (pinfunction "2_2") (pintype "input"))
      (node (ref "U2") (pin "12") (pinfunction "COL3_12") (pintype "unspecified"))
    )
    (net (code "5") (name "COL5") (class "Default")
      (node (ref "SW20") (pin "2") (pinfunction "2_2") (pintype "input"))
      (node (ref "SW34") (pin "2") (pinfunction "2_2") (pintype "input"))
      (node (ref "SW48") (pin "2") (pinfunction "2_2") (pintype "input"))
      (node (ref "SW5") (pin "2") (pinfunction "2_2") (pintype "input"))
      (node (ref "SW62") (pin "2") (pinfunction "2_2") (pintype "input"))
      (node (ref "U2") (pin "13") (pinfunction "COL4_13") (pintype "unspecified"))
    )
    (net (code "6") (name "COL6") (class "Default")
      (node (ref "SW21") (pin "2") (pinfunction "2_2") (pintype "input"))
      (node (ref "SW35") (pin "2") (pinfunction "2_2") (pintype "input"))
      (node (ref "SW49") (pin "2") (pinfunction "2_2") (pintype "input"))
      (node (ref "SW6") (pin "2") (pinfunction "2_2") (pintype "input"))
      (node (ref "SW63") (pin "2") (pinfunction "2_2") (pintype "input"))
      (node (ref "U2") (pin "14") (pinfunction "COL5_14") (pintype "unspecified"))
    )
    (net (code "7") (name "COL7") (class "Default")
      (node (ref "SW22") (pin "2") (pinfunction "2_2") (pintype "input"))
      (node (ref "SW36") (pin "2") (pinfunction "2_2") (pintype "input"))
      (node (ref "SW50") (pin "2") (pinfunction "2_2") (pintype "input"))
      (node (ref "SW64") (pin "2") (pinfunction "2_2") (pintype "input"))
      (node (ref "SW7") (pin "2") (pinfunction "2_2") (pintype "input"))
      (node (ref "SW79") (pin "2") (pinfunction "2_2") (pintype "input"))
      (node (ref "U2") (pin "15") (pinfunction "COL6_15") (pintype "unspecified"))
    )
    (net (code "8") (name "COL8") (class "Default")
      (node (ref "SW23") (pin "2") (pinfunction "2_2") (pintype "input"))
      (node (ref "SW37") (pin "2") (pinfunction "2_2") (pintype "input"))
      (node (ref "SW51") (pin "2") (pinfunction "2_2") (pintype "input"))
      (node (ref "SW65") (pin "2") (pinfunction "2_2") (pintype "input"))
      (node (ref "SW8") (pin "2") (pinfunction "2_2") (pintype "input"))
      (node (ref "U3") (pin "9") (pinfunction "COL0_9") (pintype "unspecified"))
    )
    (net (code "9") (name "COL9") (class "Default")
      (node (ref "SW24") (pin "2") (pinfunction "2_2") (pintype "input"))
      (node (ref "SW38") (pin "2") (pinfunction "2_2") (pintype "input"))
      (node (ref "SW52") (pin "2") (pinfunction "2_2") (pintype "input"))
      (node (ref "SW66") (pin "2") (pinfunction "2_2") (pintype "input"))
      (node (ref "SW9") (pin "2") (pinfunction "2_2") (pintype "input"))
      (node (ref "U3") (pin "10") (pinfunction "COL1_10") (pintype "unspecified"))
    )
    (net (code "10") (name "COL10") (class "Default")
      (node (ref "SW10") (pin "2") (pinfunction "2_2") (pintype "input"))
      (node (ref "SW25") (pin "2") (pinfunction "2_2") (pintype "input"))
      (node (ref "SW39") (pin "2") (pinfunction "2_2") (pintype "input"))
      (node (ref "SW53") (pin "2") (pinfunction "2_2") (pintype "input"))
      (node (ref "SW67") (pin "2") (pinfunction "2_2") (pintype "input"))
      (node (ref "U3") (pin "11") (pinfunction "COL2_11") (pintype "unspecified"))
    )
    (net (code "11") (name "COL11") (class "Default")
      (node (ref "SW11") (pin "2") (pinfunction "2_2") (pintype "input"))
      (node (ref "SW26") (pin "2") (pinfunction "2_2") (pintype "input"))
      (node (ref "SW40") (pin "2") (pinfunction "2_2") (pintype "input"))
      (node (ref "SW54") (pin "2") (pinfunction "2_2") (pintype "input"))
      (node (ref "SW68") (pin "2") (pinfunction "2_2") (pintype "input"))
      (node (ref "U3") (pin "12") (pinfunction "COL3_12") (pintype "unspecified"))
    )
    (net (code "12") (name "COL12") (class "Default")
      (node (ref "SW12") (pin "2") (pinfunction "2_2") (pintype "input"))
      (node (ref "SW27") (pin "2") (pinfunction "2_2") (pintype "input"))
      (node (ref "SW41") (pin "2") (pinfunction "2_2") (pintype "input"))
      (node (ref "SW55") (pin "2") (pinfunction "2_2") (pintype "input"))
      (node (ref "SW84") (pin "2") (pinfunction "2_2") (pintype "input"))
      (node (ref "U3") (pin "13") (pinfunction "COL4_13") (pintype "unspecified"))
    )
    (net (code "13") (name "COL13") (class "Default")
      (node (ref "SW13") (pin "2") (pinfunction "2_2") (pintype "input"))
      (node (ref "SW28") (pin "2") (pinfunction "2_2") (pintype "input"))
      (node (ref "SW42") (pin "2") (pinfunction "2_2") (pintype "input"))
      (node (ref "SW56") (pin "2") (pinfunction "2_2") (pintype "input"))
      (node (ref "SW70") (pin "2") (pinfunction "2_2") (pintype "input"))
      (node (ref "SW85") (pin "2") (pinfunction "2_2") (pintype "input"))
      (node (ref "U3") (pin "14") (pinfunction "COL5_14") (pintype "unspecified"))
    )
    (net (code "14") (name "COL14") (class "Default")
      (node (ref "SW14") (pin "2") (pinfunction "2_2") (pintype "input"))
      (node (ref "SW43") (pin "2") (pinfunction "2_2") (pintype "input"))
      (node (ref "SW57") (pin "2") (pinfunction "2_2") (pintype "input"))
      (node (ref "SW71") (pin "2") (pinfunction "2_2") (pintype "input"))
      (node (ref "SW86") (pin "2") (pinfunction "2_2") (pintype "input"))
      (node (ref "U3") (pin "15") (pinfunction "COL6_15") (pintype "unspecified"))
    )
    (net (code "15") (name "COL15") (class "Default")
      (node (ref "SW15") (pin "2") (pinfunction "2_2") (pintype "input"))
      (node (ref "SW29") (pin "2") (pinfunction "2_2") (pintype "input"))
      (node (ref "SW44") (pin "2") (pinfunction "2_2") (pintype "input"))
      (node (ref "SW72") (pin "2") (pinfunction "2_2") (pintype "input"))
      (node (ref "SW87") (pin "2") (pinfunction "2_2") (pintype "input"))
      (node (ref "U3") (pin "16") (pinfunction "COL7_16") (pintype "unspecified"))
    )
    (net (code "16") (name "D+") (class "Default")
      (node (ref "U5") (pin "4") (pinfunction "D+_4") (pintype "unspecified"))
      (node (ref "USB1") (pin "6") (pinfunction "DP1_6") (pintype "unspecified"))
      (node (ref "USB1") (pin "8") (pinfunction "DP2_8") (pintype "unspecified"))
    )
    (net (code "17") (name "D-") (class "Default")
      (node (ref "U5") (pin "5") (pinfunction "D-_5") (pintype "unspecified"))
      (node (ref "USB1") (pin "5") (pinfunction "DN2_5") (pintype "unspecified"))
      (node (ref "USB1") (pin "7") (pinfunction "DN1_7") (pintype "unspecified"))
    )
    (net (code "18") (name "EN") (class "Default")
      (node (ref "R6") (pin "2") (pinfunction "2_2") (pintype "input"))
      (node (ref "U4") (pin "3") (pinfunction "EN_3") (pintype "unspecified"))
      (node (ref "U7") (pin "3") (pinfunction "C_3") (pintype "unspecified"))
    )
    (net (code "19") (name "GND") (class "Default")
      (node (ref "U2") (pin "19") (pinfunction "GND_19") (pintype "unspecified"))
      (node (ref "U3") (pin "19") (pinfunction "GND_19") (pintype "unspecified"))
    )
    (net (code "20") (name "GPIO0") (class "Default")
      (node (ref "U4") (pin "25") (pinfunction "IO0_25") (pintype "unspecified"))
      (node (ref "U6") (pin "3") (pinfunction "C_3") (pintype "unspecified"))
    )
    (net (code "21") (name "Net-(D1-A)") (class "Default")
      (node (ref "D1") (pin "2") (pinfunction "A_2") (pintype "input"))
      (node (ref "SW1") (pin "1") (pinfunction "1_1") (pintype "input"))
    )
    (net (code "22") (name "Net-(D2-A)") (class "Default")
      (node (ref "D2") (pin "2") (pinfunction "A_2") (pintype "input"))
      (node (ref "SW2") (pin "1") (pinfunction "1_1") (pintype "input"))
    )
    (net (code "23") (name "Net-(D3-A)") (class "Default")
      (node (ref "D3") (pin "2") (pinfunction "A_2") (pintype "input"))
      (node (ref "SW3") (pin "1") (pinfunction "1_1") (pintype "input"))
    )
    (net (code "24") (name "Net-(D4-A)") (class "Default")
      (node (ref "D4") (pin "2") (pinfunction "A_2") (pintype "input"))
      (node (ref "SW4") (pin "1") (pinfunction "1_1") (pintype "input"))
    )
    (net (code "25") (name "Net-(D5-A)") (class "Default")
      (node (ref "D5") (pin "2") (pinfunction "A_2") (pintype "input"))
      (node (ref "SW5") (pin "1") (pinfunction "1_1") (pintype "input"))
    )
    (net (code "26") (name "Net-(D6-A)") (class "Default")
      (node (ref "D6") (pin "2") (pinfunction "A_2") (pintype "input"))
      (node (ref "SW6") (pin "1") (pinfunction "1_1") (pintype "input"))
    )
    (net (code "27") (name "Net-(D7-A)") (class "Default")
      (node (ref "D7") (pin "2") (pinfunction "A_2") (pintype "input"))
      (node (ref "SW7") (pin "1") (pinfunction "1_1") (pintype "input"))
    )
    (net (code "28") (name "Net-(D8-A)") (class "Default")
      (node (ref "D8") (pin "2") (pinfunction "A_2") (pintype "input"))
      (node (ref "SW8") (pin "1") (pinfunction "1_1") (pintype "input"))
    )
    (net (code "29") (name "Net-(D9-A)") (class "Default")
      (node (ref "D9") (pin "2") (pinfunction "A_2") (pintype "input"))
      (node (ref "SW9") (pin "1") (pinfunction "1_1") (pintype "input"))
    )
    (net (code "30") (name "Net-(D10-A)") (class "Default")
      (node (ref "D10") (pin "2") (pinfunction "A_2") (pintype "input"))
      (node (ref "SW10") (pin "1") (pinfunction "1_1") (pintype "input"))
    )
    (net (code "31") (name "Net-(D11-A)") (class "Default")
      (node (ref "D11") (pin "2") (pinfunction "A_2") (pintype "input"))
      (node (ref "SW11") (pin "1") (pinfunction "1_1") (pintype "input"))
    )
    (net (code "32") (name "Net-(D12-A)") (class "Default")
      (node (ref "D12") (pin "2") (pinfunction "A_2") (pintype "input"))
      (node (ref "SW12") (pin "1") (pinfunction "1_1") (pintype "input"))
    )
    (net (code "33") (name "Net-(D13-A)") (class "Default")
      (node (ref "D13") (pin "2") (pinfunction "A_2") (pintype "input"))
      (node (ref "SW13") (pin "1") (pinfunction "1_1") (pintype "input"))
    )
    (net (code "34") (name "Net-(D14-A)") (class "Default")
      (node (ref "D14") (pin "2") (pinfunction "A_2") (pintype "input"))
      (node (ref "SW14") (pin "1") (pinfunction "1_1") (pintype "input"))
    )
    (net (code "35") (name "Net-(D15-A)") (class "Default")
      (node (ref "D15") (pin "2") (pinfunction "A_2") (pintype "input"))
      (node (ref "SW15") (pin "1") (pinfunction "1_1") (pintype "input"))
    )
    (net (code "36") (name "Net-(D16-A)") (class "Default")
      (node (ref "D16") (pin "2") (pinfunction "A_2") (pintype "input"))
      (node (ref "SW16") (pin "1") (pinfunction "1_1") (pintype "input"))
    )
    (net (code "37") (name "Net-(D17-A)") (class "Default")
      (node (ref "D17") (pin "2") (pinfunction "A_2") (pintype "input"))
      (node (ref "SW17") (pin "1") (pinfunction "1_1") (pintype "input"))
    )
    (net (code "38") (name "Net-(D18-A)") (class "Default")
      (node (ref "D18") (pin "2") (pinfunction "A_2") (pintype "input"))
      (node (ref "SW18") (pin "1") (pinfunction "1_1") (pintype "input"))
    )
    (net (code "39") (name "Net-(D19-A)") (class "Default")
      (node (ref "D19") (pin "2") (pinfunction "A_2") (pintype "input"))
      (node (ref "SW19") (pin "1") (pinfunction "1_1") (pintype "input"))
    )
    (net (code "40") (name "Net-(D20-A)") (class "Default")
      (node (ref "D20") (pin "2") (pinfunction "A_2") (pintype "input"))
      (node (ref "SW20") (pin "1") (pinfunction "1_1") (pintype "input"))
    )
    (net (code "41") (name "Net-(D21-A)") (class "Default")
      (node (ref "D21") (pin "2") (pinfunction "A_2") (pintype "input"))
      (node (ref "SW21") (pin "1") (pinfunction "1_1") (pintype "input"))
    )
    (net (code "42") (name "Net-(D22-A)") (class "Default")
      (node (ref "D22") (pin "2") (pinfunction "A_2") (pintype "input"))
      (node (ref "SW22") (pin "1") (pinfunction "1_1") (pintype "input"))
    )
    (net (code "43") (name "Net-(D23-A)") (class "Default")
      (node (ref "D23") (pin "2") (pinfunction "A_2") (pintype "input"))
      (node (ref "SW23") (pin "1") (pinfunction "1_1") (pintype "input"))
    )
    (net (code "44") (name "Net-(D24-A)") (class "Default")
      (node (ref "D24") (pin "2") (pinfunction "A_2") (pintype "input"))
      (node (ref "SW24") (pin "1") (pinfunction "1_1") (pintype "input"))
    )
    (net (code "45") (name "Net-(D25-A)") (class "Default")
      (node (ref "D25") (pin "2") (pinfunction "A_2") (pintype "input"))
      (node (ref "SW25") (pin "1") (pinfunction "1_1") (pintype "input"))
    )
    (net (code "46") (name "Net-(D26-A)") (class "Default")
      (node (ref "D26") (pin "2") (pinfunction "A_2") (pintype "input"))
      (node (ref "SW26") (pin "1") (pinfunction "1_1") (pintype "input"))
    )
    (net (code "47") (name "Net-(D27-A)") (class "Default")
      (node (ref "D27") (pin "2") (pinfunction "A_2") (pintype "input"))
      (node (ref "SW27") (pin "1") (pinfunction "1_1") (pintype "input"))
    )
    (net (code "48") (name "Net-(D28-A)") (class "Default")
      (node (ref "D28") (pin "2") (pinfunction "A_2") (pintype "input"))
      (node (ref "SW28") (pin "1") (pinfunction "1_1") (pintype "input"))
    )
    (net (code "49") (name "Net-(D29-A)") (class "Default")
      (node (ref "D29") (pin "2") (pinfunction "A_2") (pintype "input"))
      (node (ref "SW29") (pin "1") (pinfunction "1_1") (pintype "input"))
    )
    (net (code "50") (name "Net-(D30-A)") (class "Default")
      (node (ref "D30") (pin "2") (pinfunction "A_2") (pintype "input"))
      (node (ref "SW30") (pin "1") (pinfunction "1_1") (pintype "input"))
    )
    (net (code "51") (name "Net-(D32-A)") (class "Default")
      (node (ref "D32") (pin "2") (pinfunction "A_2") (pintype "input"))
      (node (ref "SW32") (pin "1") (pinfunction "1_1") (pintype "input"))
    )
    (net (code "52") (name "Net-(D33-A)") (class "Default")
      (node (ref "D33") (pin "2") (pinfunction "A_2") (pintype "input"))
      (node (ref "SW33") (pin "1") (pinfunction "1_1") (pintype "input"))
    )
    (net (code "53") (name "Net-(D34-A)") (class "Default")
      (node (ref "D34") (pin "2") (pinfunction "A_2") (pintype "input"))
      (node (ref "SW34") (pin "1") (pinfunction "1_1") (pintype "input"))
    )
    (net (code "54") (name "Net-(D35-A)") (class "Default")
      (node (ref "D35") (pin "2") (pinfunction "A_2") (pintype "input"))
      (node (ref "SW35") (pin "1") (pinfunction "1_1") (pintype "input"))
    )
    (net (code "55") (name "Net-(D36-A)") (class "Default")
      (node (ref "D36") (pin "2") (pinfunction "A_2") (pintype "input"))
      (node (ref "SW36") (pin "1") (pinfunction "1_1") (pintype "input"))
    )
    (net (code "56") (name "Net-(D37-A)") (class "Default")
      (node (ref "D37") (pin "2") (pinfunction "A_2") (pintype "input"))
      (node (ref "SW37") (pin "1") (pinfunction "1_1") (pintype "input"))
    )
    (net (code "57") (name "Net-(D38-A)") (class "Default")
      (node (ref "D38") (pin "2") (pinfunction "A_2") (pintype "input"))
      (node (ref "SW38") (pin "1") (pinfunction "1_1") (pintype "input"))
    )
    (net (code "58") (name "Net-(D39-A)") (class "Default")
      (node (ref "D39") (pin "2") (pinfunction "A_2") (pintype "input"))
      (node (ref "SW39") (pin "1") (pinfunction "1_1") (pintype "input"))
    )
    (net (code "59") (name "Net-(D40-A)") (class "Default")
      (node (ref "D40") (pin "2") (pinfunction "A_2") (pintype "input"))
      (node (ref "SW40") (pin "1") (pinfunction "1_1") (pintype "input"))
    )
    (net (code "60") (name "Net-(D41-A)") (class "Default")
      (node (ref "D41") (pin "2") (pinfunction "A_2") (pintype "input"))
      (node (ref "SW41") (pin "1") (pinfunction "1_1") (pintype "input"))
    )
    (net (code "61") (name "Net-(D42-A)") (class "Default")
      (node (ref "D42") (pin "2") (pinfunction "A_2") (pintype "input"))
      (node (ref "SW42") (pin "1") (pinfunction "1_1") (pintype "input"))
    )
    (net (code "62") (name "Net-(D43-A)") (class "Default")
      (node (ref "D43") (pin "2") (pinfunction "A_2") (pintype "input"))
      (node (ref "SW43") (pin "1") (pinfunction "1_1") (pintype "input"))
    )
    (net (code "63") (name "Net-(D44-A)") (class "Default")
      (node (ref "D44") (pin "2") (pinfunction "A_2") (pintype "input"))
      (node (ref "SW44") (pin "1") (pinfunction "1_1") (pintype "input"))
    )
    (net (code "64") (name "Net-(D45-A)") (class "Default")
      (node (ref "D45") (pin "2") (pinfunction "A_2") (pintype "input"))
      (node (ref "SW45") (pin "1") (pinfunction "1_1") (pintype "input"))
    )
    (net (code "65") (name "Net-(D46-A)") (class "Default")
      (node (ref "D46") (pin "2") (pinfunction "A_2") (pintype "input"))
      (node (ref "SW46") (pin "1") (pinfunction "1_1") (pintype "input"))
    )
    (net (code "66") (name "Net-(D47-A)") (class "Default")
      (node (ref "D47") (pin "2") (pinfunction "A_2") (pintype "input"))
      (node (ref "SW47") (pin "1") (pinfunction "1_1") (pintype "input"))
    )
    (net (code "67") (name "Net-(D48-A)") (class "Default")
      (node (ref "D48") (pin "2") (pinfunction "A_2") (pintype "input"))
      (node (ref "SW48") (pin "1") (pinfunction "1_1") (pintype "input"))
    )
    (net (code "68") (name "Net-(D49-A)") (class "Default")
      (node (ref "D49") (pin "2") (pinfunction "A_2") (pintype "input"))
      (node (ref "SW49") (pin "1") (pinfunction "1_1") (pintype "input"))
    )
    (net (code "69") (name "Net-(D50-A)") (class "Default")
      (node (ref "D50") (pin "2") (pinfunction "A_2") (pintype "input"))
      (node (ref "SW50") (pin "1") (pinfunction "1_1") (pintype "input"))
    )
    (net (code "70") (name "Net-(D51-A)") (class "Default")
      (node (ref "D51") (pin "2") (pinfunction "A_2") (pintype "input"))
      (node (ref "SW51") (pin "1") (pinfunction "1_1") (pintype "input"))
    )
    (net (code "71") (name "Net-(D52-A)") (class "Default")
      (node (ref "D52") (pin "2") (pinfunction "A_2") (pintype "input"))
      (node (ref "SW52") (pin "1") (pinfunction "1_1") (pintype "input"))
    )
    (net (code "72") (name "Net-(D53-A)") (class "Default")
      (node (ref "D53") (pin "2") (pinfunction "A_2") (pintype "input"))
      (node (ref "SW53") (pin "1") (pinfunction "1_1") (pintype "input"))
    )
    (net (code "73") (name "Net-(D54-A)") (class "Default")
      (node (ref "D54") (pin "2") (pinfunction "A_2") (pintype "input"))
      (node (ref "SW54") (pin "1") (pinfunction "1_1") (pintype "input"))
    )
    (net (code "74") (name "Net-(D55-A)") (class "Default")
      (node (ref "D55") (pin "2") (pinfunction "A_2") (pintype "input"))
      (node (ref "SW55") (pin "1") (pinfunction "1_1") (pintype "input"))
    )
    (net (code "75") (name "Net-(D56-A)") (class "Default")
      (node (ref "D56") (pin "2") (pinfunction "A_2") (pintype "input"))
      (node (ref "SW56") (pin "1") (pinfunction "1_1") (pintype "input"))
    )
    (net (code "76") (name "Net-(D57-A)") (class "Default")
      (node (ref "D57") (pin "2") (pinfunction "A_2") (pintype "input"))
      (node (ref "SW57") (pin "1") (pinfunction "1_1") (pintype "input"))
    )
    (net (code "77") (name "Net-(D59-A)") (class "Default")
      (node (ref "D59") (pin "2") (pinfunction "A_2") (pintype "input"))
      (node (ref "SW59") (pin "1") (pinfunction "1_1") (pintype "input"))
    )
    (net (code "78") (name "Net-(D60-A)") (class "Default")
      (node (ref "D60") (pin "2") (pinfunction "A_2") (pintype "input"))
      (node (ref "SW60") (pin "1") (pinfunction "1_1") (pintype "input"))
    )
    (net (code "79") (name "Net-(D61-A)") (class "Default")
      (node (ref "D61") (pin "2") (pinfunction "A_2") (pintype "input"))
      (node (ref "SW61") (pin "1") (pinfunction "1_1") (pintype "input"))
    )
    (net (code "80") (name "Net-(D62-A)") (class "Default")
      (node (ref "D62") (pin "2") (pinfunction "A_2") (pintype "input"))
      (node (ref "SW62") (pin "1") (pinfunction "1_1") (pintype "input"))
    )
    (net (code "81") (name "Net-(D63-A)") (class "Default")
      (node (ref "D63") (pin "2") (pinfunction "A_2") (pintype "input"))
      (node (ref "SW63") (pin "1") (pinfunction "1_1") (pintype "input"))
    )
    (net (code "82") (name "Net-(D64-A)") (class "Default")
      (node (ref "D64") (pin "2") (pinfunction "A_2") (pintype "input"))
      (node (ref "SW64") (pin "1") (pinfunction "1_1") (pintype "input"))
    )
    (net (code "83") (name "Net-(D65-A)") (class "Default")
      (node (ref "D65") (pin "2") (pinfunction "A_2") (pintype "input"))
      (node (ref "SW65") (pin "1") (pinfunction "1_1") (pintype "input"))
    )
    (net (code "84") (name "Net-(D66-A)") (class "Default")
      (node (ref "D66") (pin "2") (pinfunction "A_2") (pintype "input"))
      (node (ref "SW66") (pin "1") (pinfunction "1_1") (pintype "input"))
    )
    (net (code "85") (name "Net-(D67-A)") (class "Default")
      (node (ref "D67") (pin "2") (pinfunction "A_2") (pintype "input"))
      (node (ref "SW67") (pin "1") (pinfunction "1_1") (pintype "input"))
    )
    (net (code "86") (name "Net-(D68-A)") (class "Default")
      (node (ref "D68") (pin "2") (pinfunction "A_2") (pintype "input"))
      (node (ref "SW68") (pin "1") (pinfunction "1_1") (pintype "input"))
    )
    (net (code "87") (name "Net-(D70-A)") (class "Default")
      (node (ref "D70") (pin "2") (pinfunction "A_2") (pintype "input"))
      (node (ref "SW70") (pin "1") (pinfunction "1_1") (pintype "input"))
    )
    (net (code "88") (name "Net-(D71-A)") (class "Default")
      (node (ref "D71") (pin "2") (pinfunction "A_2") (pintype "input"))
      (node (ref "SW71") (pin "1") (pinfunction "1_1") (pintype "input"))
    )
    (net (code "89") (name "Net-(D72-A)") (class "Default")
      (node (ref "D72") (pin "2") (pinfunction "A_2") (pintype "input"))
      (node (ref "SW72") (pin "1") (pinfunction "1_1") (pintype "input"))
    )
    (net (code "90") (name "Net-(D73-A)") (class "Default")
      (node (ref "D73") (pin "2") (pinfunction "A_2") (pintype "input"))
      (node (ref "SW73") (pin "1") (pinfunction "1_1") (pintype "input"))
    )
    (net (code "91") (name "Net-(D74-A)") (class "Default")
      (node (ref "D74") (pin "2") (pinfunction "A_2") (pintype "input"))
      (node (ref "SW74") (pin "1") (pinfunction "1_1") (pintype "input"))
    )
    (net (code "92") (name "Net-(D76-A)") (class "Default")
      (node (ref "D76") (pin "2") (pinfunction "A_2") (pintype "input"))
      (node (ref "SW76") (pin "1") (pinfunction "1_1") (pintype "input"))
    )
    (net (code "93") (name "Net-(D79-A)") (class "Default")
      (node (ref "D79") (pin "2") (pinfunction "A_2") (pintype "input"))
      (node (ref "SW79") (pin "1") (pinfunction "1_1") (pintype "input"))
    )
    (net (code "94") (name "Net-(D84-A)") (class "Default")
      (node (ref "D84") (pin "2") (pinfunction "A_2") (pintype "input"))
      (node (ref "SW84") (pin "1") (pinfunction "1_1") (pintype "input"))
    )
    (net (code "95") (name "Net-(D85-A)") (class "Default")
      (node (ref "D85") (pin "2") (pinfunction "A_2") (pintype "input"))
      (node (ref "SW85") (pin "1") (pinfunction "1_1") (pintype "input"))
    )
    (net (code "96") (name "Net-(D86-A)") (class "Default")
      (node (ref "D86") (pin "2") (pinfunction "A_2") (pintype "input"))
      (node (ref "SW86") (pin "1") (pinfunction "1_1") (pintype "input"))
    )
    (net (code "97") (name "Net-(D87-A)") (class "Default")
      (node (ref "D87") (pin "2") (pinfunction "A_2") (pintype "input"))
      (node (ref "SW87") (pin "1") (pinfunction "1_1") (pintype "input"))
    )
    (net (code "98") (name "Net-(U5-DTR)") (class "Default")
      (node (ref "R5") (pin "1") (pinfunction "1_1") (pintype "input"))
      (node (ref "U5") (pin "28") (pinfunction "DTR_28") (pintype "unspecified"))
      (node (ref "U6") (pin "2") (pinfunction "E_2") (pintype "unspecified"))
    )
    (net (code "99") (name "Net-(U5-RST#)") (class "Default")
      (node (ref "R1") (pin "2") (pinfunction "2_2") (pintype "input"))
      (node (ref "U5") (pin "9") (pinfunction "RST#_9") (pintype "unspecified"))
    )
    (net (code "100") (name "Net-(U5-RTS)") (class "Default")
      (node (ref "R4") (pin "1") (pinfunction "1_1") (pintype "input"))
      (node (ref "U5") (pin "24") (pinfunction "RTS_24") (pintype "unspecified"))
      (node (ref "U7") (pin "2") (pinfunction "E_2") (pintype "unspecified"))
    )
    (net (code "101") (name "Net-(U5-RXD)") (class "Default")
      (node (ref "R3") (pin "1") (pinfunction "1_1") (pintype "input"))
      (node (ref "U5") (pin "25") (pinfunction "RXD_25") (pintype "unspecified"))
    )
    (net (code "102") (name "Net-(U5-TXD)") (class "Default")
      (node (ref "R2") (pin "1") (pinfunction "1_1") (pintype "input"))
      (node (ref "U5") (pin "26") (pinfunction "TXD_26") (pintype "unspecified"))
    )
    (net (code "103") (name "Net-(U6-B)") (class "Default")
      (node (ref "R4") (pin "2") (pinfunction "2_2") (pintype "input"))
      (node (ref "U6") (pin "1") (pinfunction "B_1") (pintype "unspecified"))
    )
    (net (code "104") (name "Net-(U7-B)") (class "Default")
      (node (ref "R5") (pin "2") (pinfunction "2_2") (pintype "input"))
      (node (ref "U7") (pin "1") (pinfunction "B_1") (pintype "unspecified"))
    )
    (net (code "105") (name "ROW1") (class "Default")
      (node (ref "D1") (pin "1") (pinfunction "K_1") (pintype "input"))
      (node (ref "D10") (pin "1") (pinfunction "K_1") (pintype "input"))
      (node (ref "D11") (pin "1") (pinfunction "K_1") (pintype "input"))
      (node (ref "D12") (pin "1") (pinfunction "K_1") (pintype "input"))
      (node (ref "D13") (pin "1") (pinfunction "K_1") (pintype "input"))
      (node (ref "D14") (pin "1") (pinfunction "K_1") (pintype "input"))
      (node (ref "D15") (pin "1") (pinfunction "K_1") (pintype "input"))
      (node (ref "D2") (pin "1") (pinfunction "K_1") (pintype "input"))
      (node (ref "D3") (pin "1") (pinfunction "K_1") (pintype "input"))
      (node (ref "D4") (pin "1") (pinfunction "K_1") (pintype "input"))
      (node (ref "D5") (pin "1") (pinfunction "K_1") (pintype "input"))
      (node (ref "D6") (pin "1") (pinfunction "K_1") (pintype "input"))
      (node (ref "D7") (pin "1") (pinfunction "K_1") (pintype "input"))
      (node (ref "D8") (pin "1") (pinfunction "K_1") (pintype "input"))
      (node (ref "D9") (pin "1") (pinfunction "K_1") (pintype "input"))
      (node (ref "U2") (pin "8") (pinfunction "ROW0_8") (pintype "unspecified"))
      (node (ref "U3") (pin "8") (pinfunction "ROW0_8") (pintype "unspecified"))
    )
    (net (code "106") (name "ROW2") (class "Default")
      (node (ref "D16") (pin "1") (pinfunction "K_1") (pintype "input"))
      (node (ref "D17") (pin "1") (pinfunction "K_1") (pintype "input"))
      (node (ref "D18") (pin "1") (pinfunction "K_1") (pintype "input"))
      (node (ref "D19") (pin "1") (pinfunction "K_1") (pintype "input"))
      (node (ref "D20") (pin "1") (pinfunction "K_1") (pintype "input"))
      (node (ref "D21") (pin "1") (pinfunction "K_1") (pintype "input"))
      (node (ref "D22") (pin "1") (pinfunction "K_1") (pintype "input"))
      (node (ref "D23") (pin "1") (pinfunction "K_1") (pintype "input"))
      (node (ref "D24") (pin "1") (pinfunction "K_1") (pintype "input"))
      (node (ref "D25") (pin "1") (pinfunction "K_1") (pintype "input"))
      (node (ref "D26") (pin "1") (pinfunction "K_1") (pintype "input"))
      (node (ref "D27") (pin "1") (pinfunction "K_1") (pintype "input"))
      (node (ref "D28") (pin "1") (pinfunction "K_1") (pintype "input"))
      (node (ref "D29") (pin "1") (pinfunction "K_1") (pintype "input"))
      (node (ref "U2") (pin "7") (pinfunction "ROW1_7") (pintype "unspecified"))
      (node (ref "U3") (pin "7") (pinfunction "ROW1_7") (pintype "unspecified"))
    )
    (net (code "107") (name "ROW3") (class "Default")
      (node (ref "D30") (pin "1") (pinfunction "K_1") (pintype "input"))
      (node (ref "D32") (pin "1") (pinfunction "K_1") (pintype "input"))
      (node (ref "D33") (pin "1") (pinfunction "K_1") (pintype "input"))
      (node (ref "D34") (pin "1") (pinfunction "K_1") (pintype "input"))
      (node (ref "D35") (pin "1") (pinfunction "K_1") (pintype "input"))
      (node (ref "D36") (pin "1") (pinfunction "K_1") (pintype "input"))
      (node (ref "D37") (pin "1") (pinfunction "K_1") (pintype "input"))
      (node (ref "D38") (pin "1") (pinfunction "K_1") (pintype "input"))
      (node (ref "D39") (pin "1") (pinfunction "K_1") (pintype "input"))
      (node (ref "D40") (pin "1") (pinfunction "K_1") (pintype "input"))
      (node (ref "D41") (pin "1") (pinfunction "K_1") (pintype "input"))
      (node (ref "D42") (pin "1") (pinfunction "K_1") (pintype "input"))
      (node (ref "D43") (pin "1") (pinfunction "K_1") (pintype "input"))
      (node (ref "D44") (pin "1") (pinfunction "K_1") (pintype "input"))
      (node (ref "U2") (pin "6") (pinfunction "ROW2_6") (pintype "unspecified"))
      (node (ref "U3") (pin "6") (pinfunction "ROW2_6") (pintype "unspecified"))
    )
    (net (code "108") (name "ROW4") (class "Default")
      (node (ref "D45") (pin "1") (pinfunction "K_1") (pintype "input"))
      (node (ref "D46") (pin "1") (pinfunction "K_1") (pintype "input"))
      (node (ref "D47") (pin "1") (pinfunction "K_1") (pintype "input"))
      (node (ref "D48") (pin "1") (pinfunction "K_1") (pintype "input"))
      (node (ref "D49") (pin "1") (pinfunction "K_1") (pintype "input"))
      (node (ref "D50") (pin "1") (pinfunction "K_1") (pintype "input"))
      (node (ref "D51") (pin "1") (pinfunction "K_1") (pintype "input"))
      (node (ref "D52") (pin "1") (pinfunction "K_1") (pintype "input"))
      (node (ref "D53") (pin "1") (pinfunction "K_1") (pintype "input"))
      (node (ref "D54") (pin "1") (pinfunction "K_1") (pintype "input"))
      (node (ref "D55") (pin "1") (pinfunction "K_1") (pintype "input"))
      (node (ref "D56") (pin "1") (pinfunction "K_1") (pintype "input"))
      (node (ref "D57") (pin "1") (pinfunction "K_1") (pintype "input"))
      (node (ref "U2") (pin "5") (pinfunction "ROW3_5") (pintype "unspecified"))
      (node (ref "U3") (pin "5") (pinfunction "ROW3_5") (pintype "unspecified"))
    )
    (net (code "109") (name "ROW5") (class "Default")
      (node (ref "D59") (pin "1") (pinfunction "K_1") (pintype "input"))
      (node (ref "D60") (pin "1") (pinfunction "K_1") (pintype "input"))
      (node (ref "D61") (pin "1") (pinfunction "K_1") (pintype "input"))
      (node (ref "D62") (pin "1") (pinfunction "K_1") (pintype "input"))
      (node (ref "D63") (pin "1") (pinfunction "K_1") (pintype "input"))
      (node (ref "D64") (pin "1") (pinfunction "K_1") (pintype "input"))
      (node (ref "D65") (pin "1") (pinfunction "K_1") (pintype "input"))
      (node (ref "D66") (pin "1") (pinfunction "K_1") (pintype "input"))
      (node (ref "D67") (pin "1") (pinfunction "K_1") (pintype "input"))
      (node (ref "D68") (pin "1") (pinfunction "K_1") (pintype "input"))
      (node (ref "D70") (pin "1") (pinfunction "K_1") (pintype "input"))
      (node (ref "D71") (pin "1") (pinfunction "K_1") (pintype "input"))
      (node (ref "D72") (pin "1") (pinfunction "K_1") (pintype "input"))
      (node (ref "U2") (pin "4") (pinfunction "ROW4_4") (pintype "unspecified"))
      (node (ref "U3") (pin "4") (pinfunction "ROW4_4") (pintype "unspecified"))
    )
    (net (code "110") (name "ROW6") (class "Default")
      (node (ref "D73") (pin "1") (pinfunction "K_1") (pintype "input"))
      (node (ref "D74") (pin "1") (pinfunction "K_1") (pintype "input"))
      (node (ref "D76") (pin "1") (pinfunction "K_1") (pintype "input"))
      (node (ref "D79") (pin "1") (pinfunction "K_1") (pintype "input"))
      (node (ref "D84") (pin "1") (pinfunction "K_1") (pintype "input"))
      (node (ref "D85") (pin "1") (pinfunction "K_1") (pintype "input"))
      (node (ref "D86") (pin "1") (pinfunction "K_1") (pintype "input"))
      (node (ref "D87") (pin "1") (pinfunction "K_1") (pintype "input"))
      (node (ref "U2") (pin "3") (pinfunction "ROW5_3") (pintype "unspecified"))
      (node (ref "U3") (pin "3") (pinfunction "ROW5_3") (pintype "unspecified"))
    )
    (net (code "111") (name "RX") (class "Default")
      (node (ref "R3") (pin "2") (pinfunction "2_2") (pintype "input"))
      (node (ref "U4") (pin "34") (pinfunction "RXD0_34") (pintype "unspecified"))
    )
    (net (code "112") (name "SCL") (class "Default")
      (node (ref "U2") (pin "23") (pinfunction "SCL_23") (pintype "unspecified"))
      (node (ref "U3") (pin "23") (pinfunction "SCL_23") (pintype "unspecified"))
    )
    (net (code "113") (name "SDA") (class "Default")
      (node (ref "U2") (pin "22") (pinfunction "SDA_22") (pintype "unspecified"))
      (node (ref "U3") (pin "22") (pinfunction "SDA_22") (pintype "unspecified"))
    )
    (net (code "114") (name "TX") (class "Default")
      (node (ref "R2") (pin "2") (pinfunction "2_2") (pintype "input"))
      (node (ref "U4") (pin "35") (pinfunction "TXD0_35") (pintype "unspecified"))
    )
    (net (code "115") (name "UGND") (class "Default")
      (node (ref "C1") (pin "2") (pinfunction "2_2") (pintype "input"))
      (node (ref "U4") (pin "1") (pinfunction "GND_1") (pintype "unspecified"))
      (node (ref "U4") (pin "15") (pinfunction "GND_15") (pintype "unspecified"))
      (node (ref "U4") (pin "38") (pinfunction "GND_38") (pintype "unspecified"))
      (node (ref "U4") (pin "39") (pinfunction "GND_39") (pintype "unspecified"))
      (node (ref "U5") (pin "3") (pinfunction "GND_3") (pintype "unspecified"))
      (node (ref "USB1") (pin "1") (pinfunction "GND_1") (pintype "unspecified"))
      (node (ref "USB1") (pin "12") (pinfunction "GND_12") (pintype "unspecified"))
    )
    (net (code "116") (name "UVBS") (class "Default")
      (node (ref "U5") (pin "8") (pinfunction "VBUS_8") (pintype "unspecified"))
      (node (ref "USB1") (pin "11") (pinfunction "VBUS_11") (pintype "unspecified"))
      (node (ref "USB1") (pin "2") (pinfunction "VBUS_2") (pintype "unspecified"))
    )
    (net (code "117") (name "V33") (class "Default")
      (node (ref "C1") (pin "1") (pinfunction "1_1") (pintype "input"))
      (node (ref "R1") (pin "1") (pinfunction "1_1") (pintype "input"))
      (node (ref "R6") (pin "1") (pinfunction "1_1") (pintype "input"))
      (node (ref "U4") (pin "2") (pinfunction "VDD33_2") (pintype "unspecified"))
      (node (ref "U5") (pin "6") (pinfunction "VDD_6") (pintype "unspecified"))
      (node (ref "U5") (pin "7") (pinfunction "REGIN_7") (pintype "unspecified"))
    )
    (net (code "118") (name "unconnected-(U2-COL7-Pad16)") (class "Default")
      (node (ref "U2") (pin "16") (pinfunction "COL7_16") (pintype "unspecified"))
    )
    (net (code "119") (name "unconnected-(U2-COL8-Pad17)") (class "Default")
      (node (ref "U2") (pin "17") (pinfunction "COL8_17") (pintype "unspecified"))
    )
    (net (code "120") (name "unconnected-(U2-COL9-Pad18)") (class "Default")
      (node (ref "U2") (pin "18") (pinfunction "COL9_18") (pintype "unspecified"))
    )
    (net (code "121") (name "unconnected-(U2-EP-Pad25)") (class "Default")
      (node (ref "U2") (pin "25") (pinfunction "EP_25") (pintype "unspecified"))
    )
    (net (code "122") (name "unconnected-(U2-INT#-Pad24)") (class "Default")
      (node (ref "U2") (pin "24") (pinfunction "INT#_24") (pintype "unspecified"))
    )
    (net (code "123") (name "unconnected-(U2-RESET#-Pad20)") (class "Default")
      (node (ref "U2") (pin "20") (pinfunction "RESET#_20") (pintype "unspecified"))
    )
    (net (code "124") (name "unconnected-(U2-ROW6-Pad2)") (class "Default")
      (node (ref "U2") (pin "2") (pinfunction "ROW6_2") (pintype "unspecified"))
    )
    (net (code "125") (name "unconnected-(U2-ROW7-Pad1)") (class "Default")
      (node (ref "U2") (pin "1") (pinfunction "ROW7_1") (pintype "unspecified"))
    )
    (net (code "126") (name "unconnected-(U2-VCC-Pad21)") (class "Default")
      (node (ref "U2") (pin "21") (pinfunction "VCC_21") (pintype "unspecified"))
    )
    (net (code "127") (name "unconnected-(U3-COL8-Pad17)") (class "Default")
      (node (ref "U3") (pin "17") (pinfunction "COL8_17") (pintype "unspecified"))
    )
    (net (code "128") (name "unconnected-(U3-COL9-Pad18)") (class "Default")
      (node (ref "U3") (pin "18") (pinfunction "COL9_18") (pintype "unspecified"))
    )
    (net (code "129") (name "unconnected-(U3-EP-Pad25)") (class "Default")
      (node (ref "U3") (pin "25") (pinfunction "EP_25") (pintype "unspecified"))
    )
    (net (code "130") (name "unconnected-(U3-INT#-Pad24)") (class "Default")
      (node (ref "U3") (pin "24") (pinfunction "INT#_24") (pintype "unspecified"))
    )
    (net (code "131") (name "unconnected-(U3-RESET#-Pad20)") (class "Default")
      (node (ref "U3") (pin "20") (pinfunction "RESET#_20") (pintype "unspecified"))
    )
    (net (code "132") (name "unconnected-(U3-ROW6-Pad2)") (class "Default")
      (node (ref "U3") (pin "2") (pinfunction "ROW6_2") (pintype "unspecified"))
    )
    (net (code "133") (name "unconnected-(U3-ROW7-Pad1)") (class "Default")
      (node (ref "U3") (pin "1") (pinfunction "ROW7_1") (pintype "unspecified"))
    )
    (net (code "134") (name "unconnected-(U3-VCC-Pad21)") (class "Default")
      (node (ref "U3") (pin "21") (pinfunction "VCC_21") (pintype "unspecified"))
    )
    (net (code "135") (name "unconnected-(U4-CLK-Pad20)") (class "Default")
      (node (ref "U4") (pin "20") (pinfunction "CLK_20") (pintype "unspecified"))
    )
    (net (code "136") (name "unconnected-(U4-CMD-Pad19)") (class "Default")
      (node (ref "U4") (pin "19") (pinfunction "CMD_19") (pintype "unspecified"))
    )
    (net (code "137") (name "unconnected-(U4-IO2-Pad24)") (class "Default")
      (node (ref "U4") (pin "24") (pinfunction "IO2_24") (pintype "unspecified"))
    )
    (net (code "138") (name "unconnected-(U4-IO4-Pad26)") (class "Default")
      (node (ref "U4") (pin "26") (pinfunction "IO4_26") (pintype "unspecified"))
    )
    (net (code "139") (name "unconnected-(U4-IO5-Pad29)") (class "Default")
      (node (ref "U4") (pin "29") (pinfunction "IO5_29") (pintype "unspecified"))
    )
    (net (code "140") (name "unconnected-(U4-IO12-Pad14)") (class "Default")
      (node (ref "U4") (pin "14") (pinfunction "IO12_14") (pintype "unspecified"))
    )
    (net (code "141") (name "unconnected-(U4-IO13-Pad16)") (class "Default")
      (node (ref "U4") (pin "16") (pinfunction "IO13_16") (pintype "unspecified"))
    )
    (net (code "142") (name "unconnected-(U4-IO14-Pad13)") (class "Default")
      (node (ref "U4") (pin "13") (pinfunction "IO14_13") (pintype "unspecified"))
    )
    (net (code "143") (name "unconnected-(U4-IO15-Pad23)") (class "Default")
      (node (ref "U4") (pin "23") (pinfunction "IO15_23") (pintype "unspecified"))
    )
    (net (code "144") (name "unconnected-(U4-IO16-Pad27)") (class "Default")
      (node (ref "U4") (pin "27") (pinfunction "IO16_27") (pintype "unspecified"))
    )
    (net (code "145") (name "unconnected-(U4-IO17-Pad28)") (class "Default")
      (node (ref "U4") (pin "28") (pinfunction "IO17_28") (pintype "unspecified"))
    )
    (net (code "146") (name "unconnected-(U4-IO18-Pad30)") (class "Default")
      (node (ref "U4") (pin "30") (pinfunction "IO18_30") (pintype "unspecified"))
    )
    (net (code "147") (name "unconnected-(U4-IO19-Pad31)") (class "Default")
      (node (ref "U4") (pin "31") (pinfunction "IO19_31") (pintype "unspecified"))
    )
    (net (code "148") (name "unconnected-(U4-IO21-Pad33)") (class "Default")
      (node (ref "U4") (pin "33") (pinfunction "IO21_33") (pintype "unspecified"))
    )
    (net (code "149") (name "unconnected-(U4-IO22-Pad36)") (class "Default")
      (node (ref "U4") (pin "36") (pinfunction "IO22_36") (pintype "unspecified"))
    )
    (net (code "150") (name "unconnected-(U4-IO23-Pad37)") (class "Default")
      (node (ref "U4") (pin "37") (pinfunction "IO23_37") (pintype "unspecified"))
    )
    (net (code "151") (name "unconnected-(U4-IO25-Pad10)") (class "Default")
      (node (ref "U4") (pin "10") (pinfunction "IO25_10") (pintype "unspecified"))
    )
    (net (code "152") (name "unconnected-(U4-IO26-Pad11)") (class "Default")
      (node (ref "U4") (pin "11") (pinfunction "IO26_11") (pintype "unspecified"))
    )
    (net (code "153") (name "unconnected-(U4-IO27-Pad12)") (class "Default")
      (node (ref "U4") (pin "12") (pinfunction "IO27_12") (pintype "unspecified"))
    )
    (net (code "154") (name "unconnected-(U4-IO32-Pad8)") (class "Default")
      (node (ref "U4") (pin "8") (pinfunction "IO32_8") (pintype "unspecified"))
    )
    (net (code "155") (name "unconnected-(U4-IO33-Pad9)") (class "Default")
      (node (ref "U4") (pin "9") (pinfunction "IO33_9") (pintype "unspecified"))
    )
    (net (code "156") (name "unconnected-(U4-IO34-Pad6)") (class "Default")
      (node (ref "U4") (pin "6") (pinfunction "IO34_6") (pintype "unspecified"))
    )
    (net (code "157") (name "unconnected-(U4-IO35-Pad7)") (class "Default")
      (node (ref "U4") (pin "7") (pinfunction "IO35_7") (pintype "unspecified"))
    )
    (net (code "158") (name "unconnected-(U4-NC-Pad32)") (class "Default")
      (node (ref "U4") (pin "32") (pinfunction "NC_32") (pintype "unspecified"))
    )
    (net (code "159") (name "unconnected-(U4-SD0-Pad21)") (class "Default")
      (node (ref "U4") (pin "21") (pinfunction "SD0_21") (pintype "unspecified"))
    )
    (net (code "160") (name "unconnected-(U4-SD1-Pad22)") (class "Default")
      (node (ref "U4") (pin "22") (pinfunction "SD1_22") (pintype "unspecified"))
    )
    (net (code "161") (name "unconnected-(U4-SD2-Pad17)") (class "Default")
      (node (ref "U4") (pin "17") (pinfunction "SD2_17") (pintype "unspecified"))
    )
    (net (code "162") (name "unconnected-(U4-SD3-Pad18)") (class "Default")
      (node (ref "U4") (pin "18") (pinfunction "SD3_18") (pintype "unspecified"))
    )
    (net (code "163") (name "unconnected-(U4-SENSOR_VN-Pad5)") (class "Default")
      (node (ref "U4") (pin "5") (pinfunction "SENSOR_VN_5") (pintype "unspecified"))
    )
    (net (code "164") (name "unconnected-(U4-SENSOR_VP-Pad4)") (class "Default")
      (node (ref "U4") (pin "4") (pinfunction "SENSOR_VP_4") (pintype "unspecified"))
    )
    (net (code "165") (name "unconnected-(U5-CTS-Pad23)") (class "Default")
      (node (ref "U5") (pin "23") (pinfunction "CTS_23") (pintype "unspecified"))
    )
    (net (code "166") (name "unconnected-(U5-DCD-Pad1)") (class "Default")
      (node (ref "U5") (pin "1") (pinfunction "DCD_1") (pintype "unspecified"))
    )
    (net (code "167") (name "unconnected-(U5-DSR-Pad27)") (class "Default")
      (node (ref "U5") (pin "27") (pinfunction "DSR_27") (pintype "unspecified"))
    )
    (net (code "168") (name "unconnected-(U5-EP-Pad29)") (class "Default")
      (node (ref "U5") (pin "29") (pinfunction "EP_29") (pintype "unspecified"))
    )
    (net (code "169") (name "unconnected-(U5-NC-Pad10)") (class "Default")
      (node (ref "U5") (pin "10") (pinfunction "NC_10") (pintype "unspecified"))
    )
    (net (code "170") (name "unconnected-(U5-NC-Pad13)") (class "Default")
      (node (ref "U5") (pin "13") (pinfunction "NC_13") (pintype "unspecified"))
    )
    (net (code "171") (name "unconnected-(U5-NC-Pad14)") (class "Default")
      (node (ref "U5") (pin "14") (pinfunction "NC_14") (pintype "unspecified"))
    )
    (net (code "172") (name "unconnected-(U5-NC-Pad15)") (class "Default")
      (node (ref "U5") (pin "15") (pinfunction "NC_15") (pintype "unspecified"))
    )
    (net (code "173") (name "unconnected-(U5-NC-Pad16)") (class "Default")
      (node (ref "U5") (pin "16") (pinfunction "NC_16") (pintype "unspecified"))
    )
    (net (code "174") (name "unconnected-(U5-NC-Pad17)") (class "Default")
      (node (ref "U5") (pin "17") (pinfunction "NC_17") (pintype "unspecified"))
    )
    (net (code "175") (name "unconnected-(U5-NC-Pad18)") (class "Default")
      (node (ref "U5") (pin "18") (pinfunction "NC_18") (pintype "unspecified"))
    )
    (net (code "176") (name "unconnected-(U5-NC-Pad19)") (class "Default")
      (node (ref "U5") (pin "19") (pinfunction "NC_19") (pintype "unspecified"))
    )
    (net (code "177") (name "unconnected-(U5-NC-Pad20)") (class "Default")
      (node (ref "U5") (pin "20") (pinfunction "NC_20") (pintype "unspecified"))
    )
    (net (code "178") (name "unconnected-(U5-NC-Pad21)") (class "Default")
      (node (ref "U5") (pin "21") (pinfunction "NC_21") (pintype "unspecified"))
    )
    (net (code "179") (name "unconnected-(U5-NC-Pad22)") (class "Default")
      (node (ref "U5") (pin "22") (pinfunction "NC_22") (pintype "unspecified"))
    )
    (net (code "180") (name "unconnected-(U5-RI-Pad2)") (class "Default")
      (node (ref "U5") (pin "2") (pinfunction "RI_2") (pintype "unspecified"))
    )
    (net (code "181") (name "unconnected-(U5-SUSPEND#-Pad11)") (class "Default")
      (node (ref "U5") (pin "11") (pinfunction "SUSPEND#_11") (pintype "unspecified"))
    )
    (net (code "182") (name "unconnected-(U5-SUSPEND-Pad12)") (class "Default")
      (node (ref "U5") (pin "12") (pinfunction "SUSPEND_12") (pintype "unspecified"))
    )
    (net (code "183") (name "unconnected-(USB1-CC1-Pad4)") (class "Default")
      (node (ref "USB1") (pin "4") (pinfunction "CC1_4") (pintype "unspecified"))
    )
    (net (code "184") (name "unconnected-(USB1-CC2-Pad10)") (class "Default")
      (node (ref "USB1") (pin "10") (pinfunction "CC2_10") (pintype "unspecified"))
    )
    (net (code "185") (name "unconnected-(USB1-SBU1-Pad9)") (class "Default")
      (node (ref "USB1") (pin "9") (pinfunction "SBU1_9") (pintype "unspecified"))
    )
    (net (code "186") (name "unconnected-(USB1-SBU2-Pad3)") (class "Default")
      (node (ref "USB1") (pin "3") (pinfunction "SBU2_3") (pintype "unspecified"))
    )
    (net (code "187") (name "unconnected-(USB1-SHELL-Pad13)") (class "Default")
      (node (ref "USB1") (pin "13") (pinfunction "SHELL_13") (pintype "unspecified"))
    )
    (net (code "188") (name "unconnected-(USB1-SHELL-Pad14)") (class "Default")
      (node (ref "USB1") (pin "14") (pinfunction "SHELL_14") (pintype "unspecified"))
    )
  )
)
